# Display_LED.net
KiCad netlist of a schematic drawn in EAGLE
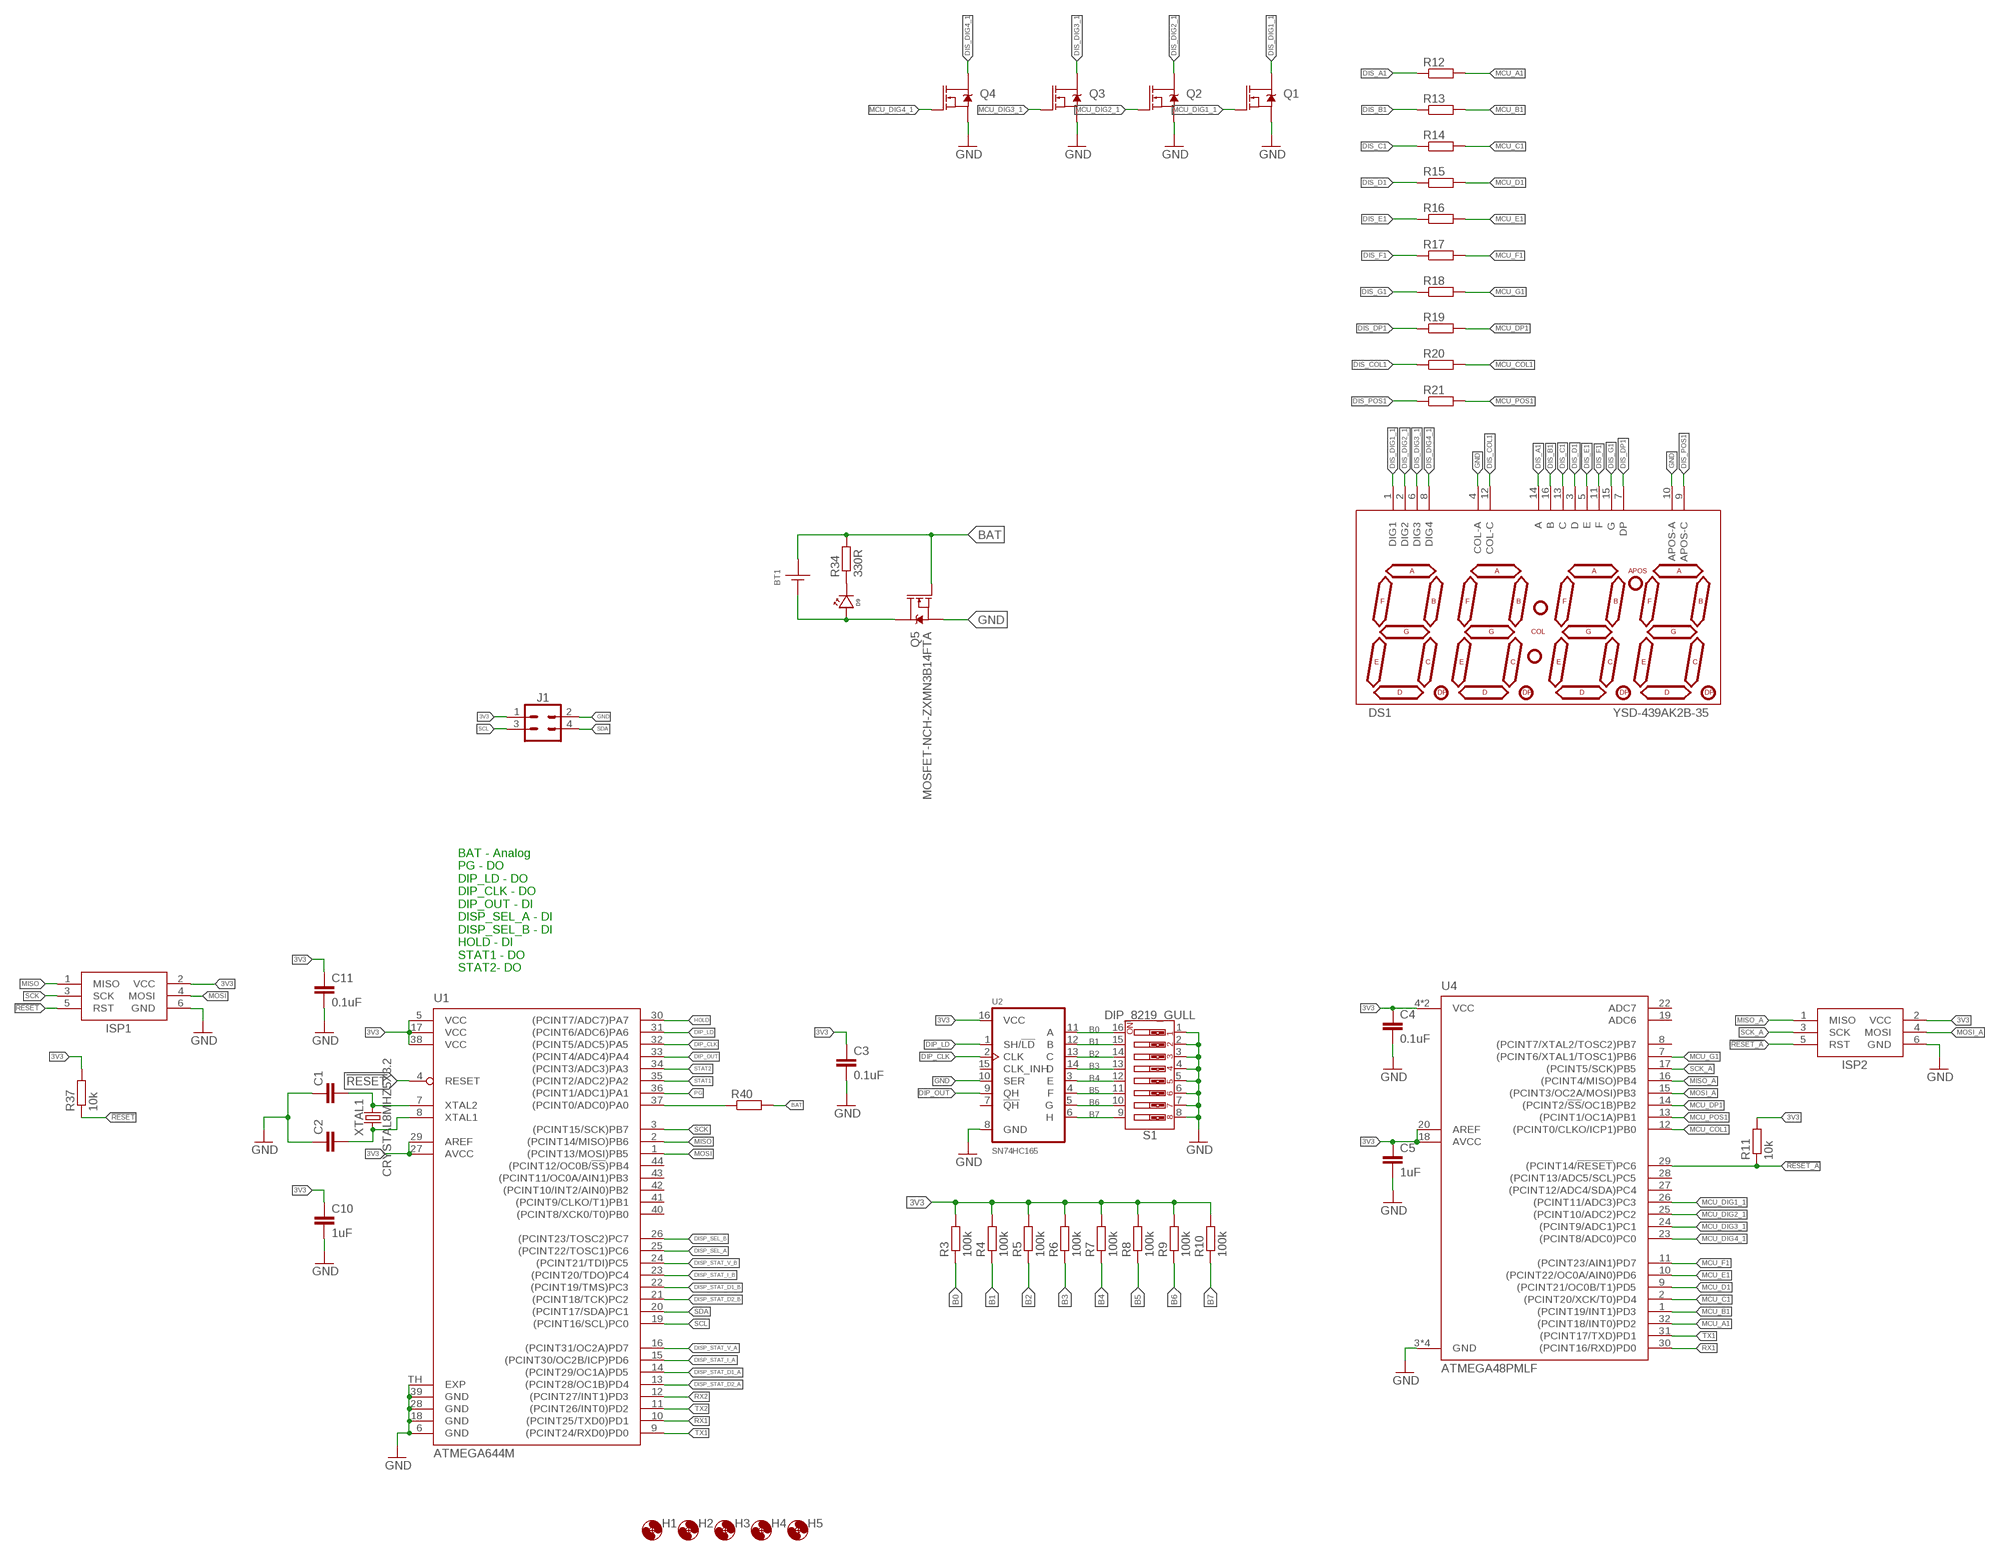
[diagram p0: schematic, sheet 1, part 1 of 2]
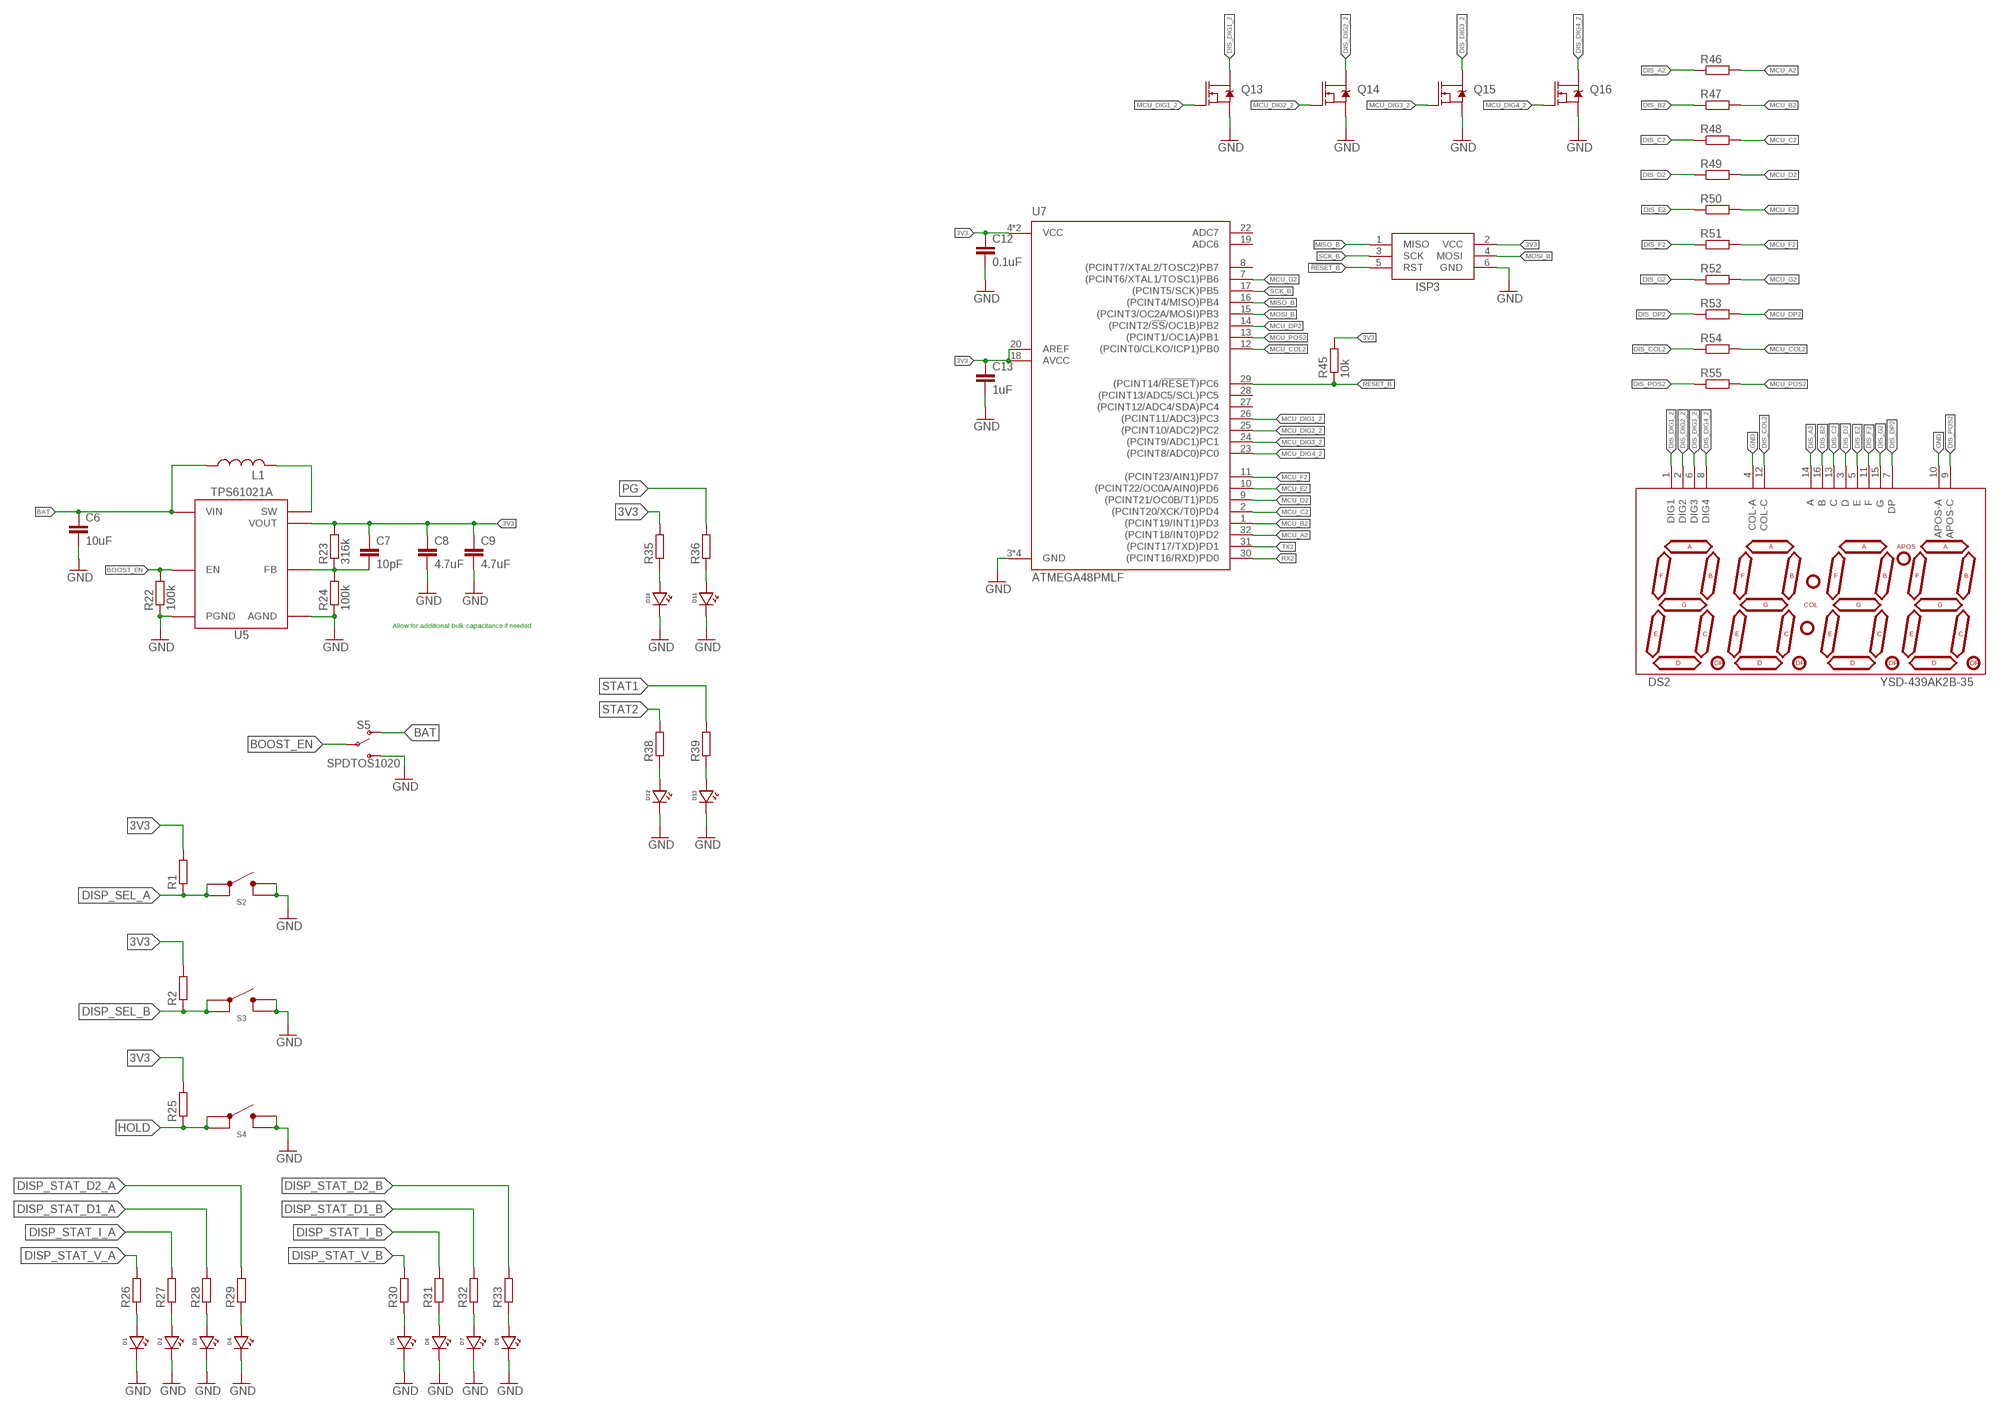
[diagram p1: schematic, sheet 1, part 2 of 2]

(export (version "E")
  (design (tool "Eeschema 10.0.6"))
  (components
    (comp (ref "BT1")
      (value "AACLIP")
      (footprint "eagle-import:BAT_AA_BK-92")
      (fields (field (name "MF") "MPD") (field (name "MPN") "BK-92"))
      (libsource (lib "eagle-import") (part "AACLIP"))
    )
    (comp (ref "C1")
      (value "C-EU12PFC0402")
      (footprint "eagle-import:C0402")
      (fields (field (name "MF") "TDK") (field (name "MPN") "CGA2B2C0G1H120J050BA"))
      (libsource (lib "eagle-import") (part "C-EUC040212PF"))
    )
    (comp (ref "C2")
      (value "C-EU12PFC0402")
      (footprint "eagle-import:C0402")
      (fields (field (name "MF") "TDK") (field (name "MPN") "CGA2B2C0G1H120J050BA"))
      (libsource (lib "eagle-import") (part "C-EUC040212PF"))
    )
    (comp (ref "C3")
      (value "0.1uF")
      (footprint "eagle-import:C0603")
      (fields (field (name "MF") "Murata") (field (name "MPN") "GCM188R71E104KA57D"))
      (libsource (lib "eagle-import") (part "C-EUC06030.1UF"))
    )
    (comp (ref "C4")
      (value "0.1uF")
      (footprint "eagle-import:C0603")
      (fields (field (name "MF") "Murata") (field (name "MPN") "GCM188R71E104KA57D"))
      (libsource (lib "eagle-import") (part "C-EUC06030.1UF"))
    )
    (comp (ref "C5")
      (value "1uF")
      (footprint "eagle-import:C0603")
      (fields (field (name "MF") "Yaiyo Yuden") (field (name "MPN") "EMK107BJ105KA-T"))
      (libsource (lib "eagle-import") (part "C-EUC06031UF"))
    )
    (comp (ref "C6")
      (value "10uF")
      (footprint "eagle-import:C0805")
      (fields (field (name "MF") "Murata") (field (name "MPN") "GRM21BR61C106KE15K"))
      (libsource (lib "eagle-import") (part "C-EUC080510UF"))
    )
    (comp (ref "C7")
      (value "10pF")
      (footprint "eagle-import:C0603")
      (fields (field (name "MF") "Yageo") (field (name "MPN") "CC0603JRNPO9BN100CC0603JRNPO9BN100"))
      (libsource (lib "eagle-import") (part "C-EUC060310PF"))
    )
    (comp (ref "C8")
      (value "4.7uF")
      (footprint "eagle-import:C0805")
      (fields (field (name "MF") "Kemet") (field (name "MPN") "C0805C475K4RACTU"))
      (libsource (lib "eagle-import") (part "C-EUC08054.7UF"))
    )
    (comp (ref "C9")
      (value "4.7uF")
      (footprint "eagle-import:C0805")
      (fields (field (name "MF") "Kemet") (field (name "MPN") "C0805C475K4RACTU"))
      (libsource (lib "eagle-import") (part "C-EUC08054.7UF"))
    )
    (comp (ref "C10")
      (value "1uF")
      (footprint "eagle-import:C0603")
      (fields (field (name "MF") "Yaiyo Yuden") (field (name "MPN") "EMK107BJ105KA-T"))
      (libsource (lib "eagle-import") (part "C-EUC06031UF"))
    )
    (comp (ref "C11")
      (value "0.1uF")
      (footprint "eagle-import:C0603")
      (fields (field (name "MF") "Yaiyo Yuden") (field (name "MPN") "EMK107BJ105KA-T"))
      (libsource (lib "eagle-import") (part "C-EUC06031UF"))
    )
    (comp (ref "C12")
      (value "0.1uF")
      (footprint "eagle-import:C0603")
      (fields (field (name "MF") "Murata") (field (name "MPN") "GCM188R71E104KA57D"))
      (libsource (lib "eagle-import") (part "C-EUC06030.1UF"))
    )
    (comp (ref "C13")
      (value "1uF")
      (footprint "eagle-import:C0603")
      (fields (field (name "MF") "Yaiyo Yuden") (field (name "MPN") "EMK107BJ105KA-T"))
      (libsource (lib "eagle-import") (part "C-EUC06031UF"))
    )
    (comp (ref "D1")
      (value "LED0603")
      (footprint "eagle-import:LED_0603")
      (libsource (lib "eagle-import") (part "LED0603"))
    )
    (comp (ref "D2")
      (value "LED0603")
      (footprint "eagle-import:LED_0603")
      (libsource (lib "eagle-import") (part "LED0603"))
    )
    (comp (ref "D3")
      (value "LED0603")
      (footprint "eagle-import:LED_0603")
      (libsource (lib "eagle-import") (part "LED0603"))
    )
    (comp (ref "D4")
      (value "LED0603")
      (footprint "eagle-import:LED_0603")
      (libsource (lib "eagle-import") (part "LED0603"))
    )
    (comp (ref "D5")
      (value "LED0603")
      (footprint "eagle-import:LED_0603")
      (libsource (lib "eagle-import") (part "LED0603"))
    )
    (comp (ref "D6")
      (value "LED0603")
      (footprint "eagle-import:LED_0603")
      (libsource (lib "eagle-import") (part "LED0603"))
    )
    (comp (ref "D7")
      (value "LED0603")
      (footprint "eagle-import:LED_0603")
      (libsource (lib "eagle-import") (part "LED0603"))
    )
    (comp (ref "D8")
      (value "LED0603")
      (footprint "eagle-import:LED_0603")
      (libsource (lib "eagle-import") (part "LED0603"))
    )
    (comp (ref "D9")
      (value "LED0603")
      (footprint "eagle-import:LED_0603")
      (libsource (lib "eagle-import") (part "LED0603"))
    )
    (comp (ref "D10")
      (value "LED0603")
      (footprint "eagle-import:LED_0603")
      (libsource (lib "eagle-import") (part "LED0603"))
    )
    (comp (ref "D11")
      (value "LED0603")
      (footprint "eagle-import:LED_0603")
      (libsource (lib "eagle-import") (part "LED0603"))
    )
    (comp (ref "D12")
      (value "LED0603")
      (footprint "eagle-import:LED_0603")
      (libsource (lib "eagle-import") (part "LED0603"))
    )
    (comp (ref "D13")
      (value "LED0603")
      (footprint "eagle-import:LED_0603")
      (libsource (lib "eagle-import") (part "LED0603"))
    )
    (comp (ref "DS1")
      (value "YSD-439AK2B-35")
      (footprint "eagle-import:7-SEGMENT-4DIGIT-YOUNGSUN")
      (libsource (lib "eagle-import") (part "LED_7-SEGMENT-4DIGIT-10MM-KGREEN"))
    )
    (comp (ref "DS2")
      (value "YSD-439AK2B-35")
      (footprint "eagle-import:7-SEGMENT-4DIGIT-YOUNGSUN")
      (libsource (lib "eagle-import") (part "LED_7-SEGMENT-4DIGIT-10MM-KGREEN"))
    )
    (comp (ref "H1")
      (value "MOUNTING_HOLE2_NP")
      (footprint "eagle-import:2_56")
      (fields (field (name "MPN") "DNP"))
      (libsource (lib "eagle-import") (part "MOUNTING_HOLE2_NP"))
    )
    (comp (ref "H2")
      (value "MOUNTING_HOLE2_NP")
      (footprint "eagle-import:2_56")
      (fields (field (name "MPN") "DNP"))
      (libsource (lib "eagle-import") (part "MOUNTING_HOLE2_NP"))
    )
    (comp (ref "H3")
      (value "MOUNTING_HOLE2_NP")
      (footprint "eagle-import:2_56")
      (fields (field (name "MPN") "DNP"))
      (libsource (lib "eagle-import") (part "MOUNTING_HOLE2_NP"))
    )
    (comp (ref "H4")
      (value "MOUNTING_HOLE2_NP")
      (footprint "eagle-import:2_56")
      (fields (field (name "MPN") "DNP"))
      (libsource (lib "eagle-import") (part "MOUNTING_HOLE2_NP"))
    )
    (comp (ref "H5")
      (value "MOUNTING_HOLE2_NP")
      (footprint "eagle-import:2_56")
      (fields (field (name "MPN") "DNP"))
      (libsource (lib "eagle-import") (part "MOUNTING_HOLE2_NP"))
    )
    (comp (ref "ISP1")
      (value "AVRISP-6")
      (footprint "eagle-import:AVRISP")
      (libsource (lib "eagle-import") (part "AVRISP-6"))
    )
    (comp (ref "ISP2")
      (value "AVRISP-6")
      (footprint "eagle-import:AVRISP")
      (libsource (lib "eagle-import") (part "AVRISP-6"))
    )
    (comp (ref "ISP3")
      (value "AVRISP-6")
      (footprint "eagle-import:AVRISP")
      (libsource (lib "eagle-import") (part "AVRISP-6"))
    )
    (comp (ref "J1")
      (value "CONN_2X2MIRCOFIT_RT")
      (footprint "eagle-import:2X2_MICROFIT_RT")
      (fields (field (name "MF") "Molex") (field (name "MPN") "0430450400"))
      (libsource (lib "eagle-import") (part "CONN_2X2MIRCOFIT_RT"))
    )
    (comp (ref "L1")
      (value "INDUCTORMAPI_3X3")
      (footprint "eagle-import:WE-MAPI(3X3)")
      (libsource (lib "eagle-import") (part "INDUCTORMAPI_3X3"))
    )
    (comp (ref "Q1")
      (value "MOSFET-NCH-2N7002P")
      (footprint "eagle-import:SOT23-3")
      (fields (field (name "MF") "Nexperia") (field (name "MPN") "2N7002P,215"))
      (libsource (lib "eagle-import") (part "MOSFET-NCH-2N7002P"))
    )
    (comp (ref "Q2")
      (value "MOSFET-NCH-2N7002P")
      (footprint "eagle-import:SOT23-3")
      (fields (field (name "MF") "Nexperia") (field (name "MPN") "2N7002P,215"))
      (libsource (lib "eagle-import") (part "MOSFET-NCH-2N7002P"))
    )
    (comp (ref "Q3")
      (value "MOSFET-NCH-2N7002P")
      (footprint "eagle-import:SOT23-3")
      (fields (field (name "MF") "Nexperia") (field (name "MPN") "2N7002P,215"))
      (libsource (lib "eagle-import") (part "MOSFET-NCH-2N7002P"))
    )
    (comp (ref "Q4")
      (value "MOSFET-NCH-2N7002P")
      (footprint "eagle-import:SOT23-3")
      (fields (field (name "MF") "Nexperia") (field (name "MPN") "2N7002P,215"))
      (libsource (lib "eagle-import") (part "MOSFET-NCH-2N7002P"))
    )
    (comp (ref "Q5")
      (value "MOSFET-NCH-ZXMN3B14FTA")
      (footprint "eagle-import:SOT23-3")
      (fields (field (name "MF") "Diodes Inc") (field (name "MPN") "ZXMN3B14FTA"))
      (libsource (lib "eagle-import") (part "MOSFET-NCH-ZXMN3B14FTA"))
    )
    (comp (ref "Q13")
      (value "MOSFET-NCH-2N7002P")
      (footprint "eagle-import:SOT23-3")
      (fields (field (name "MF") "Nexperia") (field (name "MPN") "2N7002P,215"))
      (libsource (lib "eagle-import") (part "MOSFET-NCH-2N7002P"))
    )
    (comp (ref "Q14")
      (value "MOSFET-NCH-2N7002P")
      (footprint "eagle-import:SOT23-3")
      (fields (field (name "MF") "Nexperia") (field (name "MPN") "2N7002P,215"))
      (libsource (lib "eagle-import") (part "MOSFET-NCH-2N7002P"))
    )
    (comp (ref "Q15")
      (value "MOSFET-NCH-2N7002P")
      (footprint "eagle-import:SOT23-3")
      (fields (field (name "MF") "Nexperia") (field (name "MPN") "2N7002P,215"))
      (libsource (lib "eagle-import") (part "MOSFET-NCH-2N7002P"))
    )
    (comp (ref "Q16")
      (value "MOSFET-NCH-2N7002P")
      (footprint "eagle-import:SOT23-3")
      (fields (field (name "MF") "Nexperia") (field (name "MPN") "2N7002P,215"))
      (libsource (lib "eagle-import") (part "MOSFET-NCH-2N7002P"))
    )
    (comp (ref "R1")
      (value "R-EU_10KR0603")
      (footprint "eagle-import:R0603")
      (fields
        (field (name "MF") "Yageo")
        (field (name "MPN") "RC0603FR-0710KL")
        (field (name "VALUE_PART") "10k")
      )
      (libsource (lib "eagle-import") (part "R-EU_R060310K"))
    )
    (comp (ref "R2")
      (value "R-EU_10KR0603")
      (footprint "eagle-import:R0603")
      (fields
        (field (name "MF") "Yageo")
        (field (name "MPN") "RC0603FR-0710KL")
        (field (name "VALUE_PART") "10k")
      )
      (libsource (lib "eagle-import") (part "R-EU_R060310K"))
    )
    (comp (ref "R3")
      (value "100k")
      (footprint "eagle-import:R0603")
      (fields (field (name "MF") "Yageo") (field (name "MPN") "RC0603FR-07100KL"))
      (libsource (lib "eagle-import") (part "R-EU_R0603100K"))
    )
    (comp (ref "R4")
      (value "100k")
      (footprint "eagle-import:R0603")
      (fields (field (name "MF") "Yageo") (field (name "MPN") "RC0603FR-07100KL"))
      (libsource (lib "eagle-import") (part "R-EU_R0603100K"))
    )
    (comp (ref "R5")
      (value "100k")
      (footprint "eagle-import:R0603")
      (fields (field (name "MF") "Yageo") (field (name "MPN") "RC0603FR-07100KL"))
      (libsource (lib "eagle-import") (part "R-EU_R0603100K"))
    )
    (comp (ref "R6")
      (value "100k")
      (footprint "eagle-import:R0603")
      (fields (field (name "MF") "Yageo") (field (name "MPN") "RC0603FR-07100KL"))
      (libsource (lib "eagle-import") (part "R-EU_R0603100K"))
    )
    (comp (ref "R7")
      (value "100k")
      (footprint "eagle-import:R0603")
      (fields (field (name "MF") "Yageo") (field (name "MPN") "RC0603FR-07100KL"))
      (libsource (lib "eagle-import") (part "R-EU_R0603100K"))
    )
    (comp (ref "R8")
      (value "100k")
      (footprint "eagle-import:R0603")
      (fields (field (name "MF") "Yageo") (field (name "MPN") "RC0603FR-07100KL"))
      (libsource (lib "eagle-import") (part "R-EU_R0603100K"))
    )
    (comp (ref "R9")
      (value "100k")
      (footprint "eagle-import:R0603")
      (fields (field (name "MF") "Yageo") (field (name "MPN") "RC0603FR-07100KL"))
      (libsource (lib "eagle-import") (part "R-EU_R0603100K"))
    )
    (comp (ref "R10")
      (value "100k")
      (footprint "eagle-import:R0603")
      (fields (field (name "MF") "Yageo") (field (name "MPN") "RC0603FR-07100KL"))
      (libsource (lib "eagle-import") (part "R-EU_R0603100K"))
    )
    (comp (ref "R11")
      (value "10k")
      (footprint "eagle-import:R0603")
      (fields (field (name "MF") "Yageo") (field (name "MPN") "RC0603FR-0710KL"))
      (libsource (lib "eagle-import") (part "R-EU_R060310K"))
    )
    (comp (ref "R12")
      (value "R-EU_330R0603")
      (footprint "eagle-import:R0603")
      (fields
        (field (name "MF") "Yageo")
        (field (name "MPN") "RC0603FR-07330RL")
        (field (name "VALUE_PART") "330")
      )
      (libsource (lib "eagle-import") (part "R-EU_R0603330"))
    )
    (comp (ref "R13")
      (value "R-EU_330R0603")
      (footprint "eagle-import:R0603")
      (fields
        (field (name "MF") "Yageo")
        (field (name "MPN") "RC0603FR-07330RL")
        (field (name "VALUE_PART") "330")
      )
      (libsource (lib "eagle-import") (part "R-EU_R0603330"))
    )
    (comp (ref "R14")
      (value "R-EU_330R0603")
      (footprint "eagle-import:R0603")
      (fields
        (field (name "MF") "Yageo")
        (field (name "MPN") "RC0603FR-07330RL")
        (field (name "VALUE_PART") "330")
      )
      (libsource (lib "eagle-import") (part "R-EU_R0603330"))
    )
    (comp (ref "R15")
      (value "R-EU_330R0603")
      (footprint "eagle-import:R0603")
      (fields
        (field (name "MF") "Yageo")
        (field (name "MPN") "RC0603FR-07330RL")
        (field (name "VALUE_PART") "330")
      )
      (libsource (lib "eagle-import") (part "R-EU_R0603330"))
    )
    (comp (ref "R16")
      (value "R-EU_330R0603")
      (footprint "eagle-import:R0603")
      (fields
        (field (name "MF") "Yageo")
        (field (name "MPN") "RC0603FR-07330RL")
        (field (name "VALUE_PART") "330")
      )
      (libsource (lib "eagle-import") (part "R-EU_R0603330"))
    )
    (comp (ref "R17")
      (value "R-EU_330R0603")
      (footprint "eagle-import:R0603")
      (fields
        (field (name "MF") "Yageo")
        (field (name "MPN") "RC0603FR-07330RL")
        (field (name "VALUE_PART") "330")
      )
      (libsource (lib "eagle-import") (part "R-EU_R0603330"))
    )
    (comp (ref "R18")
      (value "R-EU_330R0603")
      (footprint "eagle-import:R0603")
      (fields
        (field (name "MF") "Yageo")
        (field (name "MPN") "RC0603FR-07330RL")
        (field (name "VALUE_PART") "330")
      )
      (libsource (lib "eagle-import") (part "R-EU_R0603330"))
    )
    (comp (ref "R19")
      (value "R-EU_330R0603")
      (footprint "eagle-import:R0603")
      (fields
        (field (name "MF") "Yageo")
        (field (name "MPN") "RC0603FR-07330RL")
        (field (name "VALUE_PART") "330")
      )
      (libsource (lib "eagle-import") (part "R-EU_R0603330"))
    )
    (comp (ref "R20")
      (value "R-EU_330R0603")
      (footprint "eagle-import:R0603")
      (fields
        (field (name "MF") "Yageo")
        (field (name "MPN") "RC0603FR-07330RL")
        (field (name "VALUE_PART") "330")
      )
      (libsource (lib "eagle-import") (part "R-EU_R0603330"))
    )
    (comp (ref "R21")
      (value "R-EU_330R0603")
      (footprint "eagle-import:R0603")
      (fields
        (field (name "MF") "Yageo")
        (field (name "MPN") "RC0603FR-07330RL")
        (field (name "VALUE_PART") "330")
      )
      (libsource (lib "eagle-import") (part "R-EU_R0603330"))
    )
    (comp (ref "R22")
      (value "100k")
      (footprint "eagle-import:R0603")
      (fields (field (name "MF") "Yageo") (field (name "MPN") "RC0603FR-07100KL"))
      (libsource (lib "eagle-import") (part "R-EU_R0603100K"))
    )
    (comp (ref "R23")
      (value "316k")
      (footprint "eagle-import:R0603")
      (fields (field (name "MF") "Yageo") (field (name "MPN") "RC0603FR-07316KL"))
      (libsource (lib "eagle-import") (part "R-EU_R0603316K"))
    )
    (comp (ref "R24")
      (value "100k")
      (footprint "eagle-import:R0603")
      (fields (field (name "MF") "Yageo") (field (name "MPN") "RC0603FR-07100KL"))
      (libsource (lib "eagle-import") (part "R-EU_R0603100K"))
    )
    (comp (ref "R25")
      (value "R-EU_10KR0603")
      (footprint "eagle-import:R0603")
      (fields
        (field (name "MF") "Yageo")
        (field (name "MPN") "RC0603FR-0710KL")
        (field (name "VALUE_PART") "10k")
      )
      (libsource (lib "eagle-import") (part "R-EU_R060310K"))
    )
    (comp (ref "R26")
      (value "R-EU_330R0603")
      (footprint "eagle-import:R0603")
      (fields
        (field (name "MF") "Yageo")
        (field (name "MPN") "RC0603FR-07330RL")
        (field (name "VALUE_PART") "330")
      )
      (libsource (lib "eagle-import") (part "R-EU_R0603330"))
    )
    (comp (ref "R27")
      (value "R-EU_330R0603")
      (footprint "eagle-import:R0603")
      (fields
        (field (name "MF") "Yageo")
        (field (name "MPN") "RC0603FR-07330RL")
        (field (name "VALUE_PART") "330")
      )
      (libsource (lib "eagle-import") (part "R-EU_R0603330"))
    )
    (comp (ref "R28")
      (value "R-EU_330R0603")
      (footprint "eagle-import:R0603")
      (fields
        (field (name "MF") "Yageo")
        (field (name "MPN") "RC0603FR-07330RL")
        (field (name "VALUE_PART") "330")
      )
      (libsource (lib "eagle-import") (part "R-EU_R0603330"))
    )
    (comp (ref "R29")
      (value "R-EU_330R0603")
      (footprint "eagle-import:R0603")
      (fields
        (field (name "MF") "Yageo")
        (field (name "MPN") "RC0603FR-07330RL")
        (field (name "VALUE_PART") "330")
      )
      (libsource (lib "eagle-import") (part "R-EU_R0603330"))
    )
    (comp (ref "R30")
      (value "R-EU_330R0603")
      (footprint "eagle-import:R0603")
      (fields
        (field (name "MF") "Yageo")
        (field (name "MPN") "RC0603FR-07330RL")
        (field (name "VALUE_PART") "330")
      )
      (libsource (lib "eagle-import") (part "R-EU_R0603330"))
    )
    (comp (ref "R31")
      (value "R-EU_330R0603")
      (footprint "eagle-import:R0603")
      (fields
        (field (name "MF") "Yageo")
        (field (name "MPN") "RC0603FR-07330RL")
        (field (name "VALUE_PART") "330")
      )
      (libsource (lib "eagle-import") (part "R-EU_R0603330"))
    )
    (comp (ref "R32")
      (value "R-EU_330R0603")
      (footprint "eagle-import:R0603")
      (fields
        (field (name "MF") "Yageo")
        (field (name "MPN") "RC0603FR-07330RL")
        (field (name "VALUE_PART") "330")
      )
      (libsource (lib "eagle-import") (part "R-EU_R0603330"))
    )
    (comp (ref "R33")
      (value "R-EU_330R0603")
      (footprint "eagle-import:R0603")
      (fields
        (field (name "MF") "Yageo")
        (field (name "MPN") "RC0603FR-07330RL")
        (field (name "VALUE_PART") "330")
      )
      (libsource (lib "eagle-import") (part "R-EU_R0603330"))
    )
    (comp (ref "R34")
      (value "330R")
      (footprint "eagle-import:R0603")
      (fields
        (field (name "MF") "Yageo")
        (field (name "MPN") "RC0603FR-07330RL")
        (field (name "VALUE_PART") "330")
      )
      (libsource (lib "eagle-import") (part "R-EU_R0603330"))
    )
    (comp (ref "R35")
      (value "R-EU_330R0603")
      (footprint "eagle-import:R0603")
      (fields
        (field (name "MF") "Yageo")
        (field (name "MPN") "RC0603FR-07330RL")
        (field (name "VALUE_PART") "330")
      )
      (libsource (lib "eagle-import") (part "R-EU_R0603330"))
    )
    (comp (ref "R36")
      (value "R-EU_330R0603")
      (footprint "eagle-import:R0603")
      (fields
        (field (name "MF") "Yageo")
        (field (name "MPN") "RC0603FR-07330RL")
        (field (name "VALUE_PART") "330")
      )
      (libsource (lib "eagle-import") (part "R-EU_R0603330"))
    )
    (comp (ref "R37")
      (value "10k")
      (footprint "eagle-import:R0603")
      (fields (field (name "MF") "Yageo") (field (name "MPN") "RC0603FR-0710KL"))
      (libsource (lib "eagle-import") (part "R-EU_R060310K"))
    )
    (comp (ref "R38")
      (value "R-EU_330R0603")
      (footprint "eagle-import:R0603")
      (fields
        (field (name "MF") "Yageo")
        (field (name "MPN") "RC0603FR-07330RL")
        (field (name "VALUE_PART") "330")
      )
      (libsource (lib "eagle-import") (part "R-EU_R0603330"))
    )
    (comp (ref "R39")
      (value "R-EU_330R0603")
      (footprint "eagle-import:R0603")
      (fields
        (field (name "MF") "Yageo")
        (field (name "MPN") "RC0603FR-07330RL")
        (field (name "VALUE_PART") "330")
      )
      (libsource (lib "eagle-import") (part "R-EU_R0603330"))
    )
    (comp (ref "R40")
      (value "R-EU_1KR0603")
      (footprint "eagle-import:R0603")
      (fields
        (field (name "MF") "Yageo")
        (field (name "MPN") "AC0603FR-071KL")
        (field (name "VALUE_PART") "1k")
      )
      (libsource (lib "eagle-import") (part "R-EU_R06031K"))
    )
    (comp (ref "R45")
      (value "10k")
      (footprint "eagle-import:R0603")
      (fields (field (name "MF") "Yageo") (field (name "MPN") "RC0603FR-0710KL"))
      (libsource (lib "eagle-import") (part "R-EU_R060310K"))
    )
    (comp (ref "R46")
      (value "R-EU_330R0603")
      (footprint "eagle-import:R0603")
      (fields
        (field (name "MF") "Yageo")
        (field (name "MPN") "RC0603FR-07330RL")
        (field (name "VALUE_PART") "330")
      )
      (libsource (lib "eagle-import") (part "R-EU_R0603330"))
    )
    (comp (ref "R47")
      (value "R-EU_330R0603")
      (footprint "eagle-import:R0603")
      (fields
        (field (name "MF") "Yageo")
        (field (name "MPN") "RC0603FR-07330RL")
        (field (name "VALUE_PART") "330")
      )
      (libsource (lib "eagle-import") (part "R-EU_R0603330"))
    )
    (comp (ref "R48")
      (value "R-EU_330R0603")
      (footprint "eagle-import:R0603")
      (fields
        (field (name "MF") "Yageo")
        (field (name "MPN") "RC0603FR-07330RL")
        (field (name "VALUE_PART") "330")
      )
      (libsource (lib "eagle-import") (part "R-EU_R0603330"))
    )
    (comp (ref "R49")
      (value "R-EU_330R0603")
      (footprint "eagle-import:R0603")
      (fields
        (field (name "MF") "Yageo")
        (field (name "MPN") "RC0603FR-07330RL")
        (field (name "VALUE_PART") "330")
      )
      (libsource (lib "eagle-import") (part "R-EU_R0603330"))
    )
    (comp (ref "R50")
      (value "R-EU_330R0603")
      (footprint "eagle-import:R0603")
      (fields
        (field (name "MF") "Yageo")
        (field (name "MPN") "RC0603FR-07330RL")
        (field (name "VALUE_PART") "330")
      )
      (libsource (lib "eagle-import") (part "R-EU_R0603330"))
    )
    (comp (ref "R51")
      (value "R-EU_330R0603")
      (footprint "eagle-import:R0603")
      (fields
        (field (name "MF") "Yageo")
        (field (name "MPN") "RC0603FR-07330RL")
        (field (name "VALUE_PART") "330")
      )
      (libsource (lib "eagle-import") (part "R-EU_R0603330"))
    )
    (comp (ref "R52")
      (value "R-EU_330R0603")
      (footprint "eagle-import:R0603")
      (fields
        (field (name "MF") "Yageo")
        (field (name "MPN") "RC0603FR-07330RL")
        (field (name "VALUE_PART") "330")
      )
      (libsource (lib "eagle-import") (part "R-EU_R0603330"))
    )
    (comp (ref "R53")
      (value "R-EU_330R0603")
      (footprint "eagle-import:R0603")
      (fields
        (field (name "MF") "Yageo")
        (field (name "MPN") "RC0603FR-07330RL")
        (field (name "VALUE_PART") "330")
      )
      (libsource (lib "eagle-import") (part "R-EU_R0603330"))
    )
    (comp (ref "R54")
      (value "R-EU_330R0603")
      (footprint "eagle-import:R0603")
      (fields
        (field (name "MF") "Yageo")
        (field (name "MPN") "RC0603FR-07330RL")
        (field (name "VALUE_PART") "330")
      )
      (libsource (lib "eagle-import") (part "R-EU_R0603330"))
    )
    (comp (ref "R55")
      (value "R-EU_330R0603")
      (footprint "eagle-import:R0603")
      (fields
        (field (name "MF") "Yageo")
        (field (name "MPN") "RC0603FR-07330RL")
        (field (name "VALUE_PART") "330")
      )
      (libsource (lib "eagle-import") (part "R-EU_R0603330"))
    )
    (comp (ref "S1")
      (value "DIP_8219_GULL")
      (footprint "eagle-import:219-8_GULLWING_DIP-CTS")
      (fields (field (name "MF") "CTS") (field (name "MPN") "219-8MSTR"))
      (libsource (lib "eagle-import") (part "DIP_8219_GULL"))
    )
    (comp (ref "S2")
      (value "BUTTON6X6")
      (footprint "eagle-import:SWITCH_6MM")
      (libsource (lib "eagle-import") (part "BUTTON6X6"))
    )
    (comp (ref "S3")
      (value "BUTTON6X6")
      (footprint "eagle-import:SWITCH_6MM")
      (libsource (lib "eagle-import") (part "BUTTON6X6"))
    )
    (comp (ref "S4")
      (value "BUTTON6X6")
      (footprint "eagle-import:SWITCH_6MM")
      (libsource (lib "eagle-import") (part "BUTTON6X6"))
    )
    (comp (ref "S5")
      (value "SPDTOS1020")
      (footprint "eagle-import:OS102011MS2QN1")
      (libsource (lib "eagle-import") (part "SPDTOS1020"))
    )
    (comp (ref "U1")
      (value "ATMEGA644M")
      (footprint "eagle-import:MLF44-TH")
      (fields (field (name "MF") "Atmel") (field (name "MPN") "ATMEGA644PA-MUR"))
      (libsource (lib "eagle-import") (part "ATMEGA644M"))
    )
    (comp (ref "U2")
      (value "SN74HC165PW")
      (footprint "eagle-import:TSSOP16")
      (fields (field (name "MF") "TI") (field (name "MPN") "SN74HC165PWR"))
      (libsource (lib "eagle-import") (part "SN74HC165PW"))
    )
    (comp (ref "U4")
      (value "ATMEGA48PMLF")
      (footprint "eagle-import:MLF32-5X5")
      (fields (field (name "MF") "Microchip") (field (name "MPN") "ATMEGA48PA-MNR"))
      (libsource (lib "eagle-import") (part "ATMEGA48PMLF"))
    )
    (comp (ref "U5")
      (value "TPS61021A")
      (footprint "eagle-import:DSG0008A")
      (fields (field (name "MF") "TI") (field (name "MPN") "TPS61021ADSGT"))
      (libsource (lib "eagle-import") (part "TPS61021A"))
    )
    (comp (ref "U7")
      (value "ATMEGA48PMLF")
      (footprint "eagle-import:MLF32-5X5")
      (fields (field (name "MF") "Microchip") (field (name "MPN") "ATMEGA48PA-MNR"))
      (libsource (lib "eagle-import") (part "ATMEGA48PMLF"))
    )
    (comp (ref "XTAL1")
      (value "CRYSTAL8MHZ5X3.2")
      (footprint "eagle-import:CRYSTAL_5X3.2_2-SMD")
      (fields (field (name "MF") "TXC") (field (name "MPN") "7A-8.000MAAE-T"))
      (libsource (lib "eagle-import") (part "CRYSTAL5X3.28MHZ"))
    )
  )
  (nets
    (net (code "1") (name "/~{RESET_A}") (class "Default")
      (node (ref "ISP2") (pin "5") (pinfunction "RST_5") (pintype "output"))
      (node (ref "R11") (pin "1") (pinfunction "1_1") (pintype "passive"))
      (node (ref "U4") (pin "29") (pinfunction "(PCINT14/~{RESET})PC6_29") (pintype "bidirectional"))
    )
    (net (code "2") (name "/~{RESET_B}") (class "Default")
      (node (ref "ISP3") (pin "5") (pinfunction "RST_5") (pintype "output"))
      (node (ref "R45") (pin "1") (pinfunction "1_1") (pintype "passive"))
      (node (ref "U7") (pin "29") (pinfunction "(PCINT14/~{RESET})PC6_29") (pintype "bidirectional"))
    )
    (net (code "3") (name "/~{RESET}") (class "Default")
      (node (ref "ISP1") (pin "5") (pinfunction "RST_5") (pintype "output"))
      (node (ref "R37") (pin "1") (pinfunction "1_1") (pintype "passive"))
      (node (ref "U1") (pin "4") (pinfunction "RESET_4") (pintype "input"))
    )
    (net (code "4") (name "3V3") (class "Default")
      (node (ref "C10") (pin "1") (pinfunction "1_1") (pintype "passive"))
      (node (ref "C11") (pin "1") (pinfunction "1_1") (pintype "passive"))
      (node (ref "C12") (pin "1") (pinfunction "1_1") (pintype "passive"))
      (node (ref "C13") (pin "1") (pinfunction "1_1") (pintype "passive"))
      (node (ref "C3") (pin "1") (pinfunction "1_1") (pintype "passive"))
      (node (ref "C4") (pin "1") (pinfunction "1_1") (pintype "passive"))
      (node (ref "C5") (pin "1") (pinfunction "1_1") (pintype "passive"))
      (node (ref "C7") (pin "1") (pinfunction "1_1") (pintype "passive"))
      (node (ref "C8") (pin "1") (pinfunction "1_1") (pintype "passive"))
      (node (ref "C9") (pin "1") (pinfunction "1_1") (pintype "passive"))
      (node (ref "ISP1") (pin "2") (pinfunction "VCC_2") (pintype "power_in"))
      (node (ref "ISP2") (pin "2") (pinfunction "VCC_2") (pintype "power_in"))
      (node (ref "ISP3") (pin "2") (pinfunction "VCC_2") (pintype "power_in"))
      (node (ref "J1") (pin "1") (pinfunction "1_1") (pintype "bidirectional"))
      (node (ref "R1") (pin "2") (pinfunction "2_2") (pintype "passive"))
      (node (ref "R10") (pin "2") (pinfunction "2_2") (pintype "passive"))
      (node (ref "R11") (pin "2") (pinfunction "2_2") (pintype "passive"))
      (node (ref "R2") (pin "2") (pinfunction "2_2") (pintype "passive"))
      (node (ref "R23") (pin "2") (pinfunction "2_2") (pintype "passive"))
      (node (ref "R25") (pin "2") (pinfunction "2_2") (pintype "passive"))
      (node (ref "R3") (pin "2") (pinfunction "2_2") (pintype "passive"))
      (node (ref "R35") (pin "2") (pinfunction "2_2") (pintype "passive"))
      (node (ref "R37") (pin "2") (pinfunction "2_2") (pintype "passive"))
      (node (ref "R4") (pin "2") (pinfunction "2_2") (pintype "passive"))
      (node (ref "R45") (pin "2") (pinfunction "2_2") (pintype "passive"))
      (node (ref "R5") (pin "2") (pinfunction "2_2") (pintype "passive"))
      (node (ref "R6") (pin "2") (pinfunction "2_2") (pintype "passive"))
      (node (ref "R7") (pin "2") (pinfunction "2_2") (pintype "passive"))
      (node (ref "R8") (pin "2") (pinfunction "2_2") (pintype "passive"))
      (node (ref "R9") (pin "2") (pinfunction "2_2") (pintype "passive"))
      (node (ref "U1") (pin "17") (pinfunction "VCC_17") (pintype "power_in"))
      (node (ref "U1") (pin "27") (pinfunction "AVCC_27") (pintype "power_in"))
      (node (ref "U1") (pin "29") (pinfunction "AREF_29") (pintype "passive"))
      (node (ref "U1") (pin "38") (pinfunction "VCC_38") (pintype "power_in"))
      (node (ref "U1") (pin "5") (pinfunction "VCC_5") (pintype "power_in"))
      (node (ref "U2") (pin "16") (pinfunction "VCC_16") (pintype "power_in"))
      (node (ref "U4") (pin "18") (pinfunction "AVCC_18") (pintype "power_in"))
      (node (ref "U4") (pin "20") (pinfunction "AREF_20") (pintype "passive"))
      (node (ref "U4") (pin "4") (pinfunction "VCC_4") (pintype "power_in"))
      (node (ref "U4") (pin "6") (pinfunction "VCC_6") (pintype "power_in"))
      (node (ref "U5") (pin "3") (pinfunction "VOUT_3") (pintype "power_in"))
      (node (ref "U5") (pin "4") (pinfunction "VOUT_4") (pintype "power_in"))
      (node (ref "U7") (pin "18") (pinfunction "AVCC_18") (pintype "power_in"))
      (node (ref "U7") (pin "20") (pinfunction "AREF_20") (pintype "passive"))
      (node (ref "U7") (pin "4") (pinfunction "VCC_4") (pintype "power_in"))
      (node (ref "U7") (pin "6") (pinfunction "VCC_6") (pintype "power_in"))
    )
    (net (code "5") (name "B0") (class "Default")
      (node (ref "R3") (pin "1") (pinfunction "1_1") (pintype "passive"))
      (node (ref "S1") (pin "16") (pinfunction "16_16") (pintype "passive"))
      (node (ref "U2") (pin "11") (pinfunction "A_11") (pintype "tri_state"))
    )
    (net (code "6") (name "B1") (class "Default")
      (node (ref "R4") (pin "1") (pinfunction "1_1") (pintype "passive"))
      (node (ref "S1") (pin "15") (pinfunction "15_15") (pintype "passive"))
      (node (ref "U2") (pin "12") (pinfunction "B_12") (pintype "tri_state"))
    )
    (net (code "7") (name "B2") (class "Default")
      (node (ref "R5") (pin "1") (pinfunction "1_1") (pintype "passive"))
      (node (ref "S1") (pin "14") (pinfunction "14_14") (pintype "passive"))
      (node (ref "U2") (pin "13") (pinfunction "C_13") (pintype "tri_state"))
    )
    (net (code "8") (name "B3") (class "Default")
      (node (ref "R6") (pin "1") (pinfunction "1_1") (pintype "passive"))
      (node (ref "S1") (pin "13") (pinfunction "13_13") (pintype "passive"))
      (node (ref "U2") (pin "14") (pinfunction "D_14") (pintype "tri_state"))
    )
    (net (code "9") (name "B4") (class "Default")
      (node (ref "R7") (pin "1") (pinfunction "1_1") (pintype "passive"))
      (node (ref "S1") (pin "12") (pinfunction "12_12") (pintype "passive"))
      (node (ref "U2") (pin "3") (pinfunction "E_3") (pintype "tri_state"))
    )
    (net (code "10") (name "B5") (class "Default")
      (node (ref "R8") (pin "1") (pinfunction "1_1") (pintype "passive"))
      (node (ref "S1") (pin "11") (pinfunction "11_11") (pintype "passive"))
      (node (ref "U2") (pin "4") (pinfunction "F_4") (pintype "tri_state"))
    )
    (net (code "11") (name "B6") (class "Default")
      (node (ref "R9") (pin "1") (pinfunction "1_1") (pintype "passive"))
      (node (ref "S1") (pin "10") (pinfunction "10_10") (pintype "passive"))
      (node (ref "U2") (pin "5") (pinfunction "G_5") (pintype "tri_state"))
    )
    (net (code "12") (name "B7") (class "Default")
      (node (ref "R10") (pin "1") (pinfunction "1_1") (pintype "passive"))
      (node (ref "S1") (pin "9") (pinfunction "9_9") (pintype "passive"))
      (node (ref "U2") (pin "6") (pinfunction "H_6") (pintype "tri_state"))
    )
    (net (code "13") (name "BAT") (class "Default")
      (node (ref "BT1") (pin "POS@1") (pinfunction "+_POS@1") (pintype "power_in"))
      (node (ref "BT1") (pin "POS@2") (pinfunction "+_POS@2") (pintype "power_in"))
      (node (ref "C6") (pin "1") (pinfunction "1_1") (pintype "passive"))
      (node (ref "L1") (pin "P$1") (pinfunction "1_P$1") (pintype "passive"))
      (node (ref "Q5") (pin "1") (pinfunction "G_1") (pintype "bidirectional"))
      (node (ref "R34") (pin "2") (pinfunction "2_2") (pintype "passive"))
      (node (ref "R40") (pin "2") (pinfunction "2_2") (pintype "passive"))
      (node (ref "S5") (pin "1") (pinfunction "O_1") (pintype "passive"))
      (node (ref "U5") (pin "8") (pinfunction "VIN_8") (pintype "power_in"))
    )
    (net (code "14") (name "BOOST_EN") (class "Default")
      (node (ref "R22") (pin "2") (pinfunction "2_2") (pintype "passive"))
      (node (ref "S5") (pin "2") (pinfunction "P_2") (pintype "passive"))
      (node (ref "U5") (pin "5") (pinfunction "EN_5") (pintype "input"))
    )
    (net (code "15") (name "DIP_CLK") (class "Default")
      (node (ref "U1") (pin "32") (pinfunction "(PCINT5/ADC5)PA5_32") (pintype "bidirectional"))
      (node (ref "U2") (pin "2") (pinfunction "CLK_2") (pintype "input"))
    )
    (net (code "16") (name "DIP_LD") (class "Default")
      (node (ref "U1") (pin "31") (pinfunction "(PCINT6/ADC6)PA6_31") (pintype "bidirectional"))
      (node (ref "U2") (pin "1") (pinfunction "SH/~{LD}_1") (pintype "input"))
    )
    (net (code "17") (name "DIP_OUT") (class "Default")
      (node (ref "U1") (pin "33") (pinfunction "(PCINT4/ADC4)PA4_33") (pintype "bidirectional"))
      (node (ref "U2") (pin "9") (pinfunction "QH_9") (pintype "tri_state"))
    )
    (net (code "18") (name "DISP_SEL_A") (class "Default")
      (node (ref "R1") (pin "1") (pinfunction "1_1") (pintype "passive"))
      (node (ref "S2") (pin "1") (pinfunction "1_1") (pintype "bidirectional"))
      (node (ref "S2") (pin "2") (pinfunction "2_2") (pintype "bidirectional"))
      (node (ref "U1") (pin "25") (pinfunction "(PCINT22/TOSC1)PC6_25") (pintype "output"))
    )
    (net (code "19") (name "DISP_SEL_B") (class "Default")
      (node (ref "R2") (pin "1") (pinfunction "1_1") (pintype "passive"))
      (node (ref "S3") (pin "1") (pinfunction "1_1") (pintype "bidirectional"))
      (node (ref "S3") (pin "2") (pinfunction "2_2") (pintype "bidirectional"))
      (node (ref "U1") (pin "26") (pinfunction "(PCINT23/TOSC2)PC7_26") (pintype "output"))
    )
    (net (code "20") (name "DISP_STAT_D1_A") (class "Default")
      (node (ref "R28") (pin "2") (pinfunction "2_2") (pintype "passive"))
      (node (ref "U1") (pin "14") (pinfunction "(PCINT29/OC1A)PD5_14") (pintype "bidirectional"))
    )
    (net (code "21") (name "DISP_STAT_D1_B") (class "Default")
      (node (ref "R32") (pin "2") (pinfunction "2_2") (pintype "passive"))
      (node (ref "U1") (pin "22") (pinfunction "(PCINT19/TMS)PC3_22") (pintype "output"))
    )
    (net (code "22") (name "DISP_STAT_D2_A") (class "Default")
      (node (ref "R29") (pin "2") (pinfunction "2_2") (pintype "passive"))
      (node (ref "U1") (pin "13") (pinfunction "(PCINT28/OC1B)PD4_13") (pintype "bidirectional"))
    )
    (net (code "23") (name "DISP_STAT_D2_B") (class "Default")
      (node (ref "R33") (pin "2") (pinfunction "2_2") (pintype "passive"))
      (node (ref "U1") (pin "21") (pinfunction "(PCINT18/TCK)PC2_21") (pintype "output"))
    )
    (net (code "24") (name "DISP_STAT_I_A") (class "Default")
      (node (ref "R27") (pin "2") (pinfunction "2_2") (pintype "passive"))
      (node (ref "U1") (pin "15") (pinfunction "(PCINT30/OC2B/ICP)PD6_15") (pintype "bidirectional"))
    )
    (net (code "25") (name "DISP_STAT_I_B") (class "Default")
      (node (ref "R31") (pin "2") (pinfunction "2_2") (pintype "passive"))
      (node (ref "U1") (pin "23") (pinfunction "(PCINT20/TDO)PC4_23") (pintype "output"))
    )
    (net (code "26") (name "DISP_STAT_V_A") (class "Default")
      (node (ref "R26") (pin "2") (pinfunction "2_2") (pintype "passive"))
      (node (ref "U1") (pin "16") (pinfunction "(PCINT31/OC2A)PD7_16") (pintype "bidirectional"))
    )
    (net (code "27") (name "DISP_STAT_V_B") (class "Default")
      (node (ref "R30") (pin "2") (pinfunction "2_2") (pintype "passive"))
      (node (ref "U1") (pin "24") (pinfunction "(PCINT21/TDI)PC5_24") (pintype "output"))
    )
    (net (code "28") (name "DIS_A1") (class "Default")
      (node (ref "DS1") (pin "14") (pinfunction "A_14") (pintype "bidirectional"))
      (node (ref "R12") (pin "1") (pinfunction "1_1") (pintype "passive"))
    )
    (net (code "29") (name "DIS_A2") (class "Default")
      (node (ref "DS2") (pin "14") (pinfunction "A_14") (pintype "bidirectional"))
      (node (ref "R46") (pin "1") (pinfunction "1_1") (pintype "passive"))
    )
    (net (code "30") (name "DIS_B1") (class "Default")
      (node (ref "DS1") (pin "16") (pinfunction "B_16") (pintype "bidirectional"))
      (node (ref "R13") (pin "1") (pinfunction "1_1") (pintype "passive"))
    )
    (net (code "31") (name "DIS_B2") (class "Default")
      (node (ref "DS2") (pin "16") (pinfunction "B_16") (pintype "bidirectional"))
      (node (ref "R47") (pin "1") (pinfunction "1_1") (pintype "passive"))
    )
    (net (code "32") (name "DIS_C1") (class "Default")
      (node (ref "DS1") (pin "13") (pinfunction "C_13") (pintype "bidirectional"))
      (node (ref "R14") (pin "1") (pinfunction "1_1") (pintype "passive"))
    )
    (net (code "33") (name "DIS_C2") (class "Default")
      (node (ref "DS2") (pin "13") (pinfunction "C_13") (pintype "bidirectional"))
      (node (ref "R48") (pin "1") (pinfunction "1_1") (pintype "passive"))
    )
    (net (code "34") (name "DIS_COL1") (class "Default")
      (node (ref "DS1") (pin "12") (pinfunction "COL-C_12") (pintype "bidirectional"))
      (node (ref "R20") (pin "1") (pinfunction "1_1") (pintype "passive"))
    )
    (net (code "35") (name "DIS_COL2") (class "Default")
      (node (ref "DS2") (pin "12") (pinfunction "COL-C_12") (pintype "bidirectional"))
      (node (ref "R54") (pin "1") (pinfunction "1_1") (pintype "passive"))
    )
    (net (code "36") (name "DIS_D1") (class "Default")
      (node (ref "DS1") (pin "3") (pinfunction "D_3") (pintype "bidirectional"))
      (node (ref "R15") (pin "1") (pinfunction "1_1") (pintype "passive"))
    )
    (net (code "37") (name "DIS_D2") (class "Default")
      (node (ref "DS2") (pin "3") (pinfunction "D_3") (pintype "bidirectional"))
      (node (ref "R49") (pin "1") (pinfunction "1_1") (pintype "passive"))
    )
    (net (code "38") (name "DIS_DIG1_1") (class "Default")
      (node (ref "DS1") (pin "1") (pinfunction "DIG1_1") (pintype "bidirectional"))
      (node (ref "Q1") (pin "3") (pinfunction "D_3") (pintype "bidirectional"))
    )
    (net (code "39") (name "DIS_DIG1_2") (class "Default")
      (node (ref "DS2") (pin "1") (pinfunction "DIG1_1") (pintype "bidirectional"))
      (node (ref "Q13") (pin "3") (pinfunction "D_3") (pintype "bidirectional"))
    )
    (net (code "40") (name "DIS_DIG2_1") (class "Default")
      (node (ref "DS1") (pin "2") (pinfunction "DIG2_2") (pintype "bidirectional"))
      (node (ref "Q2") (pin "3") (pinfunction "D_3") (pintype "bidirectional"))
    )
    (net (code "41") (name "DIS_DIG2_2") (class "Default")
      (node (ref "DS2") (pin "2") (pinfunction "DIG2_2") (pintype "bidirectional"))
      (node (ref "Q14") (pin "3") (pinfunction "D_3") (pintype "bidirectional"))
    )
    (net (code "42") (name "DIS_DIG3_1") (class "Default")
      (node (ref "DS1") (pin "6") (pinfunction "DIG3_6") (pintype "bidirectional"))
      (node (ref "Q3") (pin "3") (pinfunction "D_3") (pintype "bidirectional"))
    )
    (net (code "43") (name "DIS_DIG3_2") (class "Default")
      (node (ref "DS2") (pin "6") (pinfunction "DIG3_6") (pintype "bidirectional"))
      (node (ref "Q15") (pin "3") (pinfunction "D_3") (pintype "bidirectional"))
    )
    (net (code "44") (name "DIS_DIG4_1") (class "Default")
      (node (ref "DS1") (pin "8") (pinfunction "DIG4_8") (pintype "bidirectional"))
      (node (ref "Q4") (pin "3") (pinfunction "D_3") (pintype "bidirectional"))
    )
    (net (code "45") (name "DIS_DIG4_2") (class "Default")
      (node (ref "DS2") (pin "8") (pinfunction "DIG4_8") (pintype "bidirectional"))
      (node (ref "Q16") (pin "3") (pinfunction "D_3") (pintype "bidirectional"))
    )
    (net (code "46") (name "DIS_DP1") (class "Default")
      (node (ref "DS1") (pin "7") (pinfunction "DP_7") (pintype "bidirectional"))
      (node (ref "R19") (pin "1") (pinfunction "1_1") (pintype "passive"))
    )
    (net (code "47") (name "DIS_DP2") (class "Default")
      (node (ref "DS2") (pin "7") (pinfunction "DP_7") (pintype "bidirectional"))
      (node (ref "R53") (pin "1") (pinfunction "1_1") (pintype "passive"))
    )
    (net (code "48") (name "DIS_E1") (class "Default")
      (node (ref "DS1") (pin "5") (pinfunction "E_5") (pintype "bidirectional"))
      (node (ref "R16") (pin "1") (pinfunction "1_1") (pintype "passive"))
    )
    (net (code "49") (name "DIS_E2") (class "Default")
      (node (ref "DS2") (pin "5") (pinfunction "E_5") (pintype "bidirectional"))
      (node (ref "R50") (pin "1") (pinfunction "1_1") (pintype "passive"))
    )
    (net (code "50") (name "DIS_F1") (class "Default")
      (node (ref "DS1") (pin "11") (pinfunction "F_11") (pintype "bidirectional"))
      (node (ref "R17") (pin "1") (pinfunction "1_1") (pintype "passive"))
    )
    (net (code "51") (name "DIS_F2") (class "Default")
      (node (ref "DS2") (pin "11") (pinfunction "F_11") (pintype "bidirectional"))
      (node (ref "R51") (pin "1") (pinfunction "1_1") (pintype "passive"))
    )
    (net (code "52") (name "DIS_G1") (class "Default")
      (node (ref "DS1") (pin "15") (pinfunction "G_15") (pintype "bidirectional"))
      (node (ref "R18") (pin "1") (pinfunction "1_1") (pintype "passive"))
    )
    (net (code "53") (name "DIS_G2") (class "Default")
      (node (ref "DS2") (pin "15") (pinfunction "G_15") (pintype "bidirectional"))
      (node (ref "R52") (pin "1") (pinfunction "1_1") (pintype "passive"))
    )
    (net (code "54") (name "DIS_POS1") (class "Default")
      (node (ref "DS1") (pin "9") (pinfunction "APOS-C_9") (pintype "bidirectional"))
      (node (ref "R21") (pin "1") (pinfunction "1_1") (pintype "passive"))
    )
    (net (code "55") (name "DIS_POS2") (class "Default")
      (node (ref "DS2") (pin "9") (pinfunction "APOS-C_9") (pintype "bidirectional"))
      (node (ref "R55") (pin "1") (pinfunction "1_1") (pintype "passive"))
    )
    (net (code "56") (name "GND") (class "Default")
      (node (ref "C1") (pin "1") (pinfunction "1_1") (pintype "passive"))
      (node (ref "C10") (pin "2") (pinfunction "2_2") (pintype "passive"))
      (node (ref "C11") (pin "2") (pinfunction "2_2") (pintype "passive"))
      (node (ref "C12") (pin "2") (pinfunction "2_2") (pintype "passive"))
      (node (ref "C13") (pin "2") (pinfunction "2_2") (pintype "passive"))
      (node (ref "C2") (pin "1") (pinfunction "1_1") (pintype "passive"))
      (node (ref "C3") (pin "2") (pinfunction "2_2") (pintype "passive"))
      (node (ref "C4") (pin "2") (pinfunction "2_2") (pintype "passive"))
      (node (ref "C5") (pin "2") (pinfunction "2_2") (pintype "passive"))
      (node (ref "C6") (pin "2") (pinfunction "2_2") (pintype "passive"))
      (node (ref "C8") (pin "2") (pinfunction "2_2") (pintype "passive"))
      (node (ref "C9") (pin "2") (pinfunction "2_2") (pintype "passive"))
      (node (ref "D1") (pin "CATHODE") (pinfunction "CATHODE_CATHODE") (pintype "power_in"))
      (node (ref "D10") (pin "CATHODE") (pinfunction "CATHODE_CATHODE") (pintype "power_in"))
      (node (ref "D11") (pin "CATHODE") (pinfunction "CATHODE_CATHODE") (pintype "power_in"))
      (node (ref "D12") (pin "CATHODE") (pinfunction "CATHODE_CATHODE") (pintype "power_in"))
      (node (ref "D13") (pin "CATHODE") (pinfunction "CATHODE_CATHODE") (pintype "power_in"))
      (node (ref "D2") (pin "CATHODE") (pinfunction "CATHODE_CATHODE") (pintype "power_in"))
      (node (ref "D3") (pin "CATHODE") (pinfunction "CATHODE_CATHODE") (pintype "power_in"))
      (node (ref "D4") (pin "CATHODE") (pinfunction "CATHODE_CATHODE") (pintype "power_in"))
      (node (ref "D5") (pin "CATHODE") (pinfunction "CATHODE_CATHODE") (pintype "power_in"))
      (node (ref "D6") (pin "CATHODE") (pinfunction "CATHODE_CATHODE") (pintype "power_in"))
      (node (ref "D7") (pin "CATHODE") (pinfunction "CATHODE_CATHODE") (pintype "power_in"))
      (node (ref "D8") (pin "CATHODE") (pinfunction "CATHODE_CATHODE") (pintype "power_in"))
      (node (ref "DS1") (pin "10") (pinfunction "APOS-A_10") (pintype "bidirectional"))
      (node (ref "DS1") (pin "4") (pinfunction "COL-A_4") (pintype "bidirectional"))
      (node (ref "DS2") (pin "10") (pinfunction "APOS-A_10") (pintype "bidirectional"))
      (node (ref "DS2") (pin "4") (pinfunction "COL-A_4") (pintype "bidirectional"))
      (node (ref "ISP1") (pin "6") (pinfunction "GND_6") (pintype "power_in"))
      (node (ref "ISP2") (pin "6") (pinfunction "GND_6") (pintype "power_in"))
      (node (ref "ISP3") (pin "6") (pinfunction "GND_6") (pintype "power_in"))
      (node (ref "J1") (pin "2") (pinfunction "2_2") (pintype "bidirectional"))
      (node (ref "Q1") (pin "2") (pinfunction "S_2") (pintype "bidirectional"))
      (node (ref "Q13") (pin "2") (pinfunction "S_2") (pintype "bidirectional"))
      (node (ref "Q14") (pin "2") (pinfunction "S_2") (pintype "bidirectional"))
      (node (ref "Q15") (pin "2") (pinfunction "S_2") (pintype "bidirectional"))
      (node (ref "Q16") (pin "2") (pinfunction "S_2") (pintype "bidirectional"))
      (node (ref "Q2") (pin "2") (pinfunction "S_2") (pintype "bidirectional"))
      (node (ref "Q3") (pin "2") (pinfunction "S_2") (pintype "bidirectional"))
      (node (ref "Q4") (pin "2") (pinfunction "S_2") (pintype "bidirectional"))
      (node (ref "Q5") (pin "2") (pinfunction "S_2") (pintype "bidirectional"))
      (node (ref "R22") (pin "1") (pinfunction "1_1") (pintype "passive"))
      (node (ref "R24") (pin "1") (pinfunction "1_1") (pintype "passive"))
      (node (ref "S1") (pin "1") (pinfunction "1_1") (pintype "passive"))
      (node (ref "S1") (pin "2") (pinfunction "2_2") (pintype "passive"))
      (node (ref "S1") (pin "3") (pinfunction "3_3") (pintype "passive"))
      (node (ref "S1") (pin "4") (pinfunction "4_4") (pintype "passive"))
      (node (ref "S1") (pin "5") (pinfunction "5_5") (pintype "passive"))
      (node (ref "S1") (pin "6") (pinfunction "6_6") (pintype "passive"))
      (node (ref "S1") (pin "7") (pinfunction "7_7") (pintype "passive"))
      (node (ref "S1") (pin "8") (pinfunction "8_8") (pintype "passive"))
      (node (ref "S2") (pin "3") (pinfunction "3_3") (pintype "bidirectional"))
      (node (ref "S2") (pin "4") (pinfunction "4_4") (pintype "bidirectional"))
      (node (ref "S3") (pin "3") (pinfunction "3_3") (pintype "bidirectional"))
      (node (ref "S3") (pin "4") (pinfunction "4_4") (pintype "bidirectional"))
      (node (ref "S4") (pin "3") (pinfunction "3_3") (pintype "bidirectional"))
      (node (ref "S4") (pin "4") (pinfunction "4_4") (pintype "bidirectional"))
      (node (ref "S5") (pin "3") (pinfunction "S_3") (pintype "passive"))
      (node (ref "U1") (pin "18") (pinfunction "GND_18") (pintype "power_in"))
      (node (ref "U1") (pin "28") (pinfunction "GND_28") (pintype "power_in"))
      (node (ref "U1") (pin "39") (pinfunction "GND_39") (pintype "power_in"))
      (node (ref "U1") (pin "6") (pinfunction "GND_6") (pintype "power_in"))
      (node (ref "U1") (pin "TH") (pinfunction "EXP_TH") (pintype "power_in"))
      (node (ref "U2") (pin "10") (pinfunction "SER_10") (pintype "input"))
      (node (ref "U2") (pin "8") (pinfunction "GND_8") (pintype "power_in"))
      (node (ref "U4") (pin "21") (pinfunction "GND_21") (pintype "power_in"))
      (node (ref "U4") (pin "3") (pinfunction "GND_3") (pintype "power_in"))
      (node (ref "U4") (pin "5") (pinfunction "GND_5") (pintype "power_in"))
      (node (ref "U4") (pin "TH") (pinfunction "GND_TH") (pintype "power_in"))
      (node (ref "U5") (pin "1") (pinfunction "AGND_1") (pintype "power_in"))
      (node (ref "U5") (pin "EP@1") (pinfunction "PGND_EP@1") (pintype "power_in"))
      (node (ref "U5") (pin "EP@2") (pinfunction "PGND_EP@2") (pintype "power_in"))
      (node (ref "U5") (pin "EP@3") (pinfunction "PGND_EP@3") (pintype "power_in"))
      (node (ref "U7") (pin "21") (pinfunction "GND_21") (pintype "power_in"))
      (node (ref "U7") (pin "3") (pinfunction "GND_3") (pintype "power_in"))
      (node (ref "U7") (pin "5") (pinfunction "GND_5") (pintype "power_in"))
      (node (ref "U7") (pin "TH") (pinfunction "GND_TH") (pintype "power_in"))
    )
    (net (code "57") (name "HOLD") (class "Default")
      (node (ref "R25") (pin "1") (pinfunction "1_1") (pintype "passive"))
      (node (ref "S4") (pin "1") (pinfunction "1_1") (pintype "bidirectional"))
      (node (ref "S4") (pin "2") (pinfunction "2_2") (pintype "bidirectional"))
      (node (ref "U1") (pin "30") (pinfunction "(PCINT7/ADC7)PA7_30") (pintype "bidirectional"))
    )
    (net (code "58") (name "MCU_A1") (class "Default")
      (node (ref "R12") (pin "2") (pinfunction "2_2") (pintype "passive"))
      (node (ref "U4") (pin "32") (pinfunction "(PCINT18/INT0)PD2_32") (pintype "bidirectional"))
    )
    (net (code "59") (name "MCU_A2") (class "Default")
      (node (ref "R46") (pin "2") (pinfunction "2_2") (pintype "passive"))
      (node (ref "U7") (pin "32") (pinfunction "(PCINT18/INT0)PD2_32") (pintype "bidirectional"))
    )
    (net (code "60") (name "MCU_B1") (class "Default")
      (node (ref "R13") (pin "2") (pinfunction "2_2") (pintype "passive"))
      (node (ref "U4") (pin "1") (pinfunction "(PCINT19/INT1)PD3_1") (pintype "bidirectional"))
    )
    (net (code "61") (name "MCU_B2") (class "Default")
      (node (ref "R47") (pin "2") (pinfunction "2_2") (pintype "passive"))
      (node (ref "U7") (pin "1") (pinfunction "(PCINT19/INT1)PD3_1") (pintype "bidirectional"))
    )
    (net (code "62") (name "MCU_C1") (class "Default")
      (node (ref "R14") (pin "2") (pinfunction "2_2") (pintype "passive"))
      (node (ref "U4") (pin "2") (pinfunction "(PCINT20/XCK/T0)PD4_2") (pintype "bidirectional"))
    )
    (net (code "63") (name "MCU_C2") (class "Default")
      (node (ref "R48") (pin "2") (pinfunction "2_2") (pintype "passive"))
      (node (ref "U7") (pin "2") (pinfunction "(PCINT20/XCK/T0)PD4_2") (pintype "bidirectional"))
    )
    (net (code "64") (name "MCU_COL1") (class "Default")
      (node (ref "R20") (pin "2") (pinfunction "2_2") (pintype "passive"))
      (node (ref "U4") (pin "12") (pinfunction "(PCINT0/CLKO/ICP1)PB0_12") (pintype "bidirectional"))
    )
    (net (code "65") (name "MCU_COL2") (class "Default")
      (node (ref "R54") (pin "2") (pinfunction "2_2") (pintype "passive"))
      (node (ref "U7") (pin "12") (pinfunction "(PCINT0/CLKO/ICP1)PB0_12") (pintype "bidirectional"))
    )
    (net (code "66") (name "MCU_D1") (class "Default")
      (node (ref "R15") (pin "2") (pinfunction "2_2") (pintype "passive"))
      (node (ref "U4") (pin "9") (pinfunction "(PCINT21/OC0B/T1)PD5_9") (pintype "bidirectional"))
    )
    (net (code "67") (name "MCU_D2") (class "Default")
      (node (ref "R49") (pin "2") (pinfunction "2_2") (pintype "passive"))
      (node (ref "U7") (pin "9") (pinfunction "(PCINT21/OC0B/T1)PD5_9") (pintype "bidirectional"))
    )
    (net (code "68") (name "MCU_DIG1_1") (class "Default")
      (node (ref "Q1") (pin "1") (pinfunction "G_1") (pintype "bidirectional"))
      (node (ref "U4") (pin "26") (pinfunction "(PCINT11/ADC3)PC3_26") (pintype "bidirectional"))
    )
    (net (code "69") (name "MCU_DIG1_2") (class "Default")
      (node (ref "Q13") (pin "1") (pinfunction "G_1") (pintype "bidirectional"))
      (node (ref "U7") (pin "26") (pinfunction "(PCINT11/ADC3)PC3_26") (pintype "bidirectional"))
    )
    (net (code "70") (name "MCU_DIG2_1") (class "Default")
      (node (ref "Q2") (pin "1") (pinfunction "G_1") (pintype "bidirectional"))
      (node (ref "U4") (pin "25") (pinfunction "(PCINT10/ADC2)PC2_25") (pintype "bidirectional"))
    )
    (net (code "71") (name "MCU_DIG2_2") (class "Default")
      (node (ref "Q14") (pin "1") (pinfunction "G_1") (pintype "bidirectional"))
      (node (ref "U7") (pin "25") (pinfunction "(PCINT10/ADC2)PC2_25") (pintype "bidirectional"))
    )
    (net (code "72") (name "MCU_DIG3_1") (class "Default")
      (node (ref "Q3") (pin "1") (pinfunction "G_1") (pintype "bidirectional"))
      (node (ref "U4") (pin "24") (pinfunction "(PCINT9/ADC1)PC1_24") (pintype "bidirectional"))
    )
    (net (code "73") (name "MCU_DIG3_2") (class "Default")
      (node (ref "Q15") (pin "1") (pinfunction "G_1") (pintype "bidirectional"))
      (node (ref "U7") (pin "24") (pinfunction "(PCINT9/ADC1)PC1_24") (pintype "bidirectional"))
    )
    (net (code "74") (name "MCU_DIG4_1") (class "Default")
      (node (ref "Q4") (pin "1") (pinfunction "G_1") (pintype "bidirectional"))
      (node (ref "U4") (pin "23") (pinfunction "(PCINT8/ADC0)PC0_23") (pintype "bidirectional"))
    )
    (net (code "75") (name "MCU_DIG4_2") (class "Default")
      (node (ref "Q16") (pin "1") (pinfunction "G_1") (pintype "bidirectional"))
      (node (ref "U7") (pin "23") (pinfunction "(PCINT8/ADC0)PC0_23") (pintype "bidirectional"))
    )
    (net (code "76") (name "MCU_DP1") (class "Default")
      (node (ref "R19") (pin "2") (pinfunction "2_2") (pintype "passive"))
      (node (ref "U4") (pin "14") (pinfunction "(PCINT2/~{SS}/OC1B)PB2_14") (pintype "bidirectional"))
    )
    (net (code "77") (name "MCU_DP2") (class "Default")
      (node (ref "R53") (pin "2") (pinfunction "2_2") (pintype "passive"))
      (node (ref "U7") (pin "14") (pinfunction "(PCINT2/~{SS}/OC1B)PB2_14") (pintype "bidirectional"))
    )
    (net (code "78") (name "MCU_E1") (class "Default")
      (node (ref "R16") (pin "2") (pinfunction "2_2") (pintype "passive"))
      (node (ref "U4") (pin "10") (pinfunction "(PCINT22/OC0A/AIN0)PD6_10") (pintype "bidirectional"))
    )
    (net (code "79") (name "MCU_E2") (class "Default")
      (node (ref "R50") (pin "2") (pinfunction "2_2") (pintype "passive"))
      (node (ref "U7") (pin "10") (pinfunction "(PCINT22/OC0A/AIN0)PD6_10") (pintype "bidirectional"))
    )
    (net (code "80") (name "MCU_F1") (class "Default")
      (node (ref "R17") (pin "2") (pinfunction "2_2") (pintype "passive"))
      (node (ref "U4") (pin "11") (pinfunction "(PCINT23/AIN1)PD7_11") (pintype "bidirectional"))
    )
    (net (code "81") (name "MCU_F2") (class "Default")
      (node (ref "R51") (pin "2") (pinfunction "2_2") (pintype "passive"))
      (node (ref "U7") (pin "11") (pinfunction "(PCINT23/AIN1)PD7_11") (pintype "bidirectional"))
    )
    (net (code "82") (name "MCU_G1") (class "Default")
      (node (ref "R18") (pin "2") (pinfunction "2_2") (pintype "passive"))
      (node (ref "U4") (pin "7") (pinfunction "(PCINT6/XTAL1/TOSC1)PB6_7") (pintype "bidirectional"))
    )
    (net (code "83") (name "MCU_G2") (class "Default")
      (node (ref "R52") (pin "2") (pinfunction "2_2") (pintype "passive"))
      (node (ref "U7") (pin "7") (pinfunction "(PCINT6/XTAL1/TOSC1)PB6_7") (pintype "bidirectional"))
    )
    (net (code "84") (name "MCU_POS1") (class "Default")
      (node (ref "R21") (pin "2") (pinfunction "2_2") (pintype "passive"))
      (node (ref "U4") (pin "13") (pinfunction "(PCINT1/OC1A)PB1_13") (pintype "bidirectional"))
    )
    (net (code "85") (name "MCU_POS2") (class "Default")
      (node (ref "R55") (pin "2") (pinfunction "2_2") (pintype "passive"))
      (node (ref "U7") (pin "13") (pinfunction "(PCINT1/OC1A)PB1_13") (pintype "bidirectional"))
    )
    (net (code "86") (name "MISO") (class "Default")
      (node (ref "ISP1") (pin "1") (pinfunction "MISO_1") (pintype "input"))
      (node (ref "U1") (pin "2") (pinfunction "(PCINT14/MISO)PB6_2") (pintype "bidirectional"))
    )
    (net (code "87") (name "MISO_A") (class "Default")
      (node (ref "ISP2") (pin "1") (pinfunction "MISO_1") (pintype "input"))
      (node (ref "U4") (pin "16") (pinfunction "(PCINT4/MISO)PB4_16") (pintype "bidirectional"))
    )
    (net (code "88") (name "MISO_B") (class "Default")
      (node (ref "ISP3") (pin "1") (pinfunction "MISO_1") (pintype "input"))
      (node (ref "U7") (pin "16") (pinfunction "(PCINT4/MISO)PB4_16") (pintype "bidirectional"))
    )
    (net (code "89") (name "MOSI") (class "Default")
      (node (ref "ISP1") (pin "4") (pinfunction "MOSI_4") (pintype "output"))
      (node (ref "U1") (pin "1") (pinfunction "(PCINT13/MOSI)PB5_1") (pintype "bidirectional"))
    )
    (net (code "90") (name "MOSI_A") (class "Default")
      (node (ref "ISP2") (pin "4") (pinfunction "MOSI_4") (pintype "output"))
      (node (ref "U4") (pin "15") (pinfunction "(PCINT3/OC2A/MOSI)PB3_15") (pintype "bidirectional"))
    )
    (net (code "91") (name "MOSI_B") (class "Default")
      (node (ref "ISP3") (pin "4") (pinfunction "MOSI_4") (pintype "output"))
      (node (ref "U7") (pin "15") (pinfunction "(PCINT3/OC2A/MOSI)PB3_15") (pintype "bidirectional"))
    )
    (net (code "92") (name "Net-(D1-PadANODE)") (class "Default")
      (node (ref "D1") (pin "ANODE") (pinfunction "ANODE_ANODE") (pintype "power_in"))
      (node (ref "R26") (pin "1") (pinfunction "1_1") (pintype "passive"))
    )
    (net (code "93") (name "Net-(D2-PadANODE)") (class "Default")
      (node (ref "D2") (pin "ANODE") (pinfunction "ANODE_ANODE") (pintype "power_in"))
      (node (ref "R27") (pin "1") (pinfunction "1_1") (pintype "passive"))
    )
    (net (code "94") (name "Net-(D3-PadANODE)") (class "Default")
      (node (ref "D3") (pin "ANODE") (pinfunction "ANODE_ANODE") (pintype "power_in"))
      (node (ref "R28") (pin "1") (pinfunction "1_1") (pintype "passive"))
    )
    (net (code "95") (name "Net-(D4-PadANODE)") (class "Default")
      (node (ref "D4") (pin "ANODE") (pinfunction "ANODE_ANODE") (pintype "power_in"))
      (node (ref "R29") (pin "1") (pinfunction "1_1") (pintype "passive"))
    )
    (net (code "96") (name "Net-(D5-PadANODE)") (class "Default")
      (node (ref "D5") (pin "ANODE") (pinfunction "ANODE_ANODE") (pintype "power_in"))
      (node (ref "R30") (pin "1") (pinfunction "1_1") (pintype "passive"))
    )
    (net (code "97") (name "Net-(D6-PadANODE)") (class "Default")
      (node (ref "D6") (pin "ANODE") (pinfunction "ANODE_ANODE") (pintype "power_in"))
      (node (ref "R31") (pin "1") (pinfunction "1_1") (pintype "passive"))
    )
    (net (code "98") (name "Net-(D7-PadANODE)") (class "Default")
      (node (ref "D7") (pin "ANODE") (pinfunction "ANODE_ANODE") (pintype "power_in"))
      (node (ref "R32") (pin "1") (pinfunction "1_1") (pintype "passive"))
    )
    (net (code "99") (name "Net-(D8-PadANODE)") (class "Default")
      (node (ref "D8") (pin "ANODE") (pinfunction "ANODE_ANODE") (pintype "power_in"))
      (node (ref "R33") (pin "1") (pinfunction "1_1") (pintype "passive"))
    )
    (net (code "100") (name "Net-(D9-PadCATHODE)") (class "Default")
      (node (ref "D9") (pin "CATHODE") (pinfunction "CATHODE_CATHODE") (pintype "power_in"))
      (node (ref "R34") (pin "1") (pinfunction "1_1") (pintype "passive"))
    )
    (net (code "101") (name "Net-(D10-PadANODE)") (class "Default")
      (node (ref "D10") (pin "ANODE") (pinfunction "ANODE_ANODE") (pintype "power_in"))
      (node (ref "R35") (pin "1") (pinfunction "1_1") (pintype "passive"))
    )
    (net (code "102") (name "Net-(D11-PadANODE)") (class "Default")
      (node (ref "D11") (pin "ANODE") (pinfunction "ANODE_ANODE") (pintype "power_in"))
      (node (ref "R36") (pin "1") (pinfunction "1_1") (pintype "passive"))
    )
    (net (code "103") (name "Net-(D12-PadANODE)") (class "Default")
      (node (ref "D12") (pin "ANODE") (pinfunction "ANODE_ANODE") (pintype "power_in"))
      (node (ref "R38") (pin "1") (pinfunction "1_1") (pintype "passive"))
    )
    (net (code "104") (name "Net-(D13-PadANODE)") (class "Default")
      (node (ref "D13") (pin "ANODE") (pinfunction "ANODE_ANODE") (pintype "power_in"))
      (node (ref "R39") (pin "1") (pinfunction "1_1") (pintype "passive"))
    )
    (net (code "105") (name "Net-(L1-2)") (class "Default")
      (node (ref "L1") (pin "P$2") (pinfunction "2_P$2") (pintype "passive"))
      (node (ref "U5") (pin "6") (pinfunction "SW_6") (pintype "power_in"))
      (node (ref "U5") (pin "7") (pinfunction "SW_7") (pintype "power_in"))
    )
    (net (code "106") (name "Net-(Q5-D)") (class "Default")
      (node (ref "BT1") (pin "NEG@1") (pinfunction "-_NEG@1") (pintype "power_in"))
      (node (ref "BT1") (pin "NEG@2") (pinfunction "-_NEG@2") (pintype "power_in"))
      (node (ref "D9") (pin "ANODE") (pinfunction "ANODE_ANODE") (pintype "power_in"))
      (node (ref "Q5") (pin "3") (pinfunction "D_3") (pintype "bidirectional"))
    )
    (net (code "107") (name "Net-(U1-(PCINT0{slash}ADC0)PA0)") (class "Default")
      (node (ref "R40") (pin "1") (pinfunction "1_1") (pintype "passive"))
      (node (ref "U1") (pin "37") (pinfunction "(PCINT0/ADC0)PA0_37") (pintype "bidirectional"))
    )
    (net (code "108") (name "Net-(U1-XTAL1)") (class "Default")
      (node (ref "C2") (pin "2") (pinfunction "2_2") (pintype "passive"))
      (node (ref "U1") (pin "8") (pinfunction "XTAL1_8") (pintype "bidirectional"))
      (node (ref "XTAL1") (pin "OSC1") (pinfunction "1_OSC1") (pintype "passive"))
    )
    (net (code "109") (name "Net-(U1-XTAL2)") (class "Default")
      (node (ref "C1") (pin "2") (pinfunction "2_2") (pintype "passive"))
      (node (ref "U1") (pin "7") (pinfunction "XTAL2_7") (pintype "bidirectional"))
      (node (ref "XTAL1") (pin "OSC2") (pinfunction "2_OSC2") (pintype "passive"))
    )
    (net (code "110") (name "Net-(U5-FB)") (class "Default")
      (node (ref "C7") (pin "2") (pinfunction "2_2") (pintype "passive"))
      (node (ref "R23") (pin "1") (pinfunction "1_1") (pintype "passive"))
      (node (ref "R24") (pin "2") (pinfunction "2_2") (pintype "passive"))
      (node (ref "U5") (pin "2") (pinfunction "FB_2") (pintype "input"))
    )
    (net (code "111") (name "PG") (class "Default")
      (node (ref "R36") (pin "2") (pinfunction "2_2") (pintype "passive"))
      (node (ref "U1") (pin "36") (pinfunction "(PCINT1/ADC1)PA1_36") (pintype "bidirectional"))
    )
    (net (code "112") (name "RX1") (class "Default")
      (node (ref "U1") (pin "10") (pinfunction "(PCINT25/TXD0)PD1_10") (pintype "bidirectional"))
      (node (ref "U4") (pin "30") (pinfunction "(PCINT16/RXD)PD0_30") (pintype "bidirectional"))
    )
    (net (code "113") (name "RX2") (class "Default")
      (node (ref "U1") (pin "12") (pinfunction "(PCINT27/INT1)PD3_12") (pintype "bidirectional"))
      (node (ref "U7") (pin "30") (pinfunction "(PCINT16/RXD)PD0_30") (pintype "bidirectional"))
    )
    (net (code "114") (name "SCK") (class "Default")
      (node (ref "ISP1") (pin "3") (pinfunction "SCK_3") (pintype "output"))
      (node (ref "U1") (pin "3") (pinfunction "(PCINT15/SCK)PB7_3") (pintype "bidirectional"))
    )
    (net (code "115") (name "SCK_A") (class "Default")
      (node (ref "ISP2") (pin "3") (pinfunction "SCK_3") (pintype "output"))
      (node (ref "U4") (pin "17") (pinfunction "(PCINT5/SCK)PB5_17") (pintype "bidirectional"))
    )
    (net (code "116") (name "SCK_B") (class "Default")
      (node (ref "ISP3") (pin "3") (pinfunction "SCK_3") (pintype "output"))
      (node (ref "U7") (pin "17") (pinfunction "(PCINT5/SCK)PB5_17") (pintype "bidirectional"))
    )
    (net (code "117") (name "SCL") (class "Default")
      (node (ref "J1") (pin "3") (pinfunction "3_3") (pintype "bidirectional"))
      (node (ref "U1") (pin "19") (pinfunction "(PCINT16/SCL)PC0_19") (pintype "output"))
    )
    (net (code "118") (name "SDA") (class "Default")
      (node (ref "J1") (pin "4") (pinfunction "4_4") (pintype "bidirectional"))
      (node (ref "U1") (pin "20") (pinfunction "(PCINT17/SDA)PC1_20") (pintype "output"))
    )
    (net (code "119") (name "STAT1") (class "Default")
      (node (ref "R39") (pin "2") (pinfunction "2_2") (pintype "passive"))
      (node (ref "U1") (pin "35") (pinfunction "(PCINT2/ADC2)PA2_35") (pintype "bidirectional"))
    )
    (net (code "120") (name "STAT2") (class "Default")
      (node (ref "R38") (pin "2") (pinfunction "2_2") (pintype "passive"))
      (node (ref "U1") (pin "34") (pinfunction "(PCINT3/ADC3)PA3_34") (pintype "bidirectional"))
    )
    (net (code "121") (name "TX1") (class "Default")
      (node (ref "U1") (pin "9") (pinfunction "(PCINT24/RXD0)PD0_9") (pintype "bidirectional"))
      (node (ref "U4") (pin "31") (pinfunction "(PCINT17/TXD)PD1_31") (pintype "bidirectional"))
    )
    (net (code "122") (name "TX2") (class "Default")
      (node (ref "U1") (pin "11") (pinfunction "(PCINT26/INT0)PD2_11") (pintype "bidirectional"))
      (node (ref "U7") (pin "31") (pinfunction "(PCINT17/TXD)PD1_31") (pintype "bidirectional"))
    )
    (net (code "123") (name "unconnected-(U1-(PCINT8{slash}XCK0{slash}T0)PB0-Pad40)") (class "Default")
      (node (ref "U1") (pin "40") (pinfunction "(PCINT8/XCK0/T0)PB0_40") (pintype "bidirectional"))
    )
    (net (code "124") (name "unconnected-(U1-(PCINT9{slash}CLKO{slash}T1)PB1-Pad41)") (class "Default")
      (node (ref "U1") (pin "41") (pinfunction "(PCINT9/CLKO/T1)PB1_41") (pintype "bidirectional"))
    )
    (net (code "125") (name "unconnected-(U1-(PCINT10{slash}INT2{slash}AIN0)PB2-Pad42)") (class "Default")
      (node (ref "U1") (pin "42") (pinfunction "(PCINT10/INT2/AIN0)PB2_42") (pintype "bidirectional"))
    )
    (net (code "126") (name "unconnected-(U1-(PCINT11{slash}OC0A{slash}AIN1)PB3-Pad43)") (class "Default")
      (node (ref "U1") (pin "43") (pinfunction "(PCINT11/OC0A/AIN1)PB3_43") (pintype "bidirectional"))
    )
    (net (code "127") (name "unconnected-(U1-(PCINT12{slash}OC0B{slash}~{SS})PB4-Pad44)") (class "Default")
      (node (ref "U1") (pin "44") (pinfunction "(PCINT12/OC0B/~{SS})PB4_44") (pintype "bidirectional"))
    )
    (net (code "128") (name "unconnected-(U2-CLK_INH-Pad15)") (class "Default")
      (node (ref "U2") (pin "15") (pinfunction "CLK_INH_15") (pintype "input"))
    )
    (net (code "129") (name "unconnected-(U2-~{QH}-Pad7)") (class "Default")
      (node (ref "U2") (pin "7") (pinfunction "~{QH}_7") (pintype "input"))
    )
    (net (code "130") (name "unconnected-(U4-(PCINT7{slash}XTAL2{slash}TOSC2)PB7-Pad8)") (class "Default")
      (node (ref "U4") (pin "8") (pinfunction "(PCINT7/XTAL2/TOSC2)PB7_8") (pintype "bidirectional"))
    )
    (net (code "131") (name "unconnected-(U4-(PCINT12{slash}ADC4{slash}SDA)PC4-Pad27)") (class "Default")
      (node (ref "U4") (pin "27") (pinfunction "(PCINT12/ADC4/SDA)PC4_27") (pintype "bidirectional"))
    )
    (net (code "132") (name "unconnected-(U4-(PCINT13{slash}ADC5{slash}SCL)PC5-Pad28)") (class "Default")
      (node (ref "U4") (pin "28") (pinfunction "(PCINT13/ADC5/SCL)PC5_28") (pintype "bidirectional"))
    )
    (net (code "133") (name "unconnected-(U4-ADC6-Pad19)") (class "Default")
      (node (ref "U4") (pin "19") (pinfunction "ADC6_19") (pintype "input"))
    )
    (net (code "134") (name "unconnected-(U4-ADC7-Pad22)") (class "Default")
      (node (ref "U4") (pin "22") (pinfunction "ADC7_22") (pintype "input"))
    )
    (net (code "135") (name "unconnected-(U7-(PCINT7{slash}XTAL2{slash}TOSC2)PB7-Pad8)") (class "Default")
      (node (ref "U7") (pin "8") (pinfunction "(PCINT7/XTAL2/TOSC2)PB7_8") (pintype "bidirectional"))
    )
    (net (code "136") (name "unconnected-(U7-(PCINT12{slash}ADC4{slash}SDA)PC4-Pad27)") (class "Default")
      (node (ref "U7") (pin "27") (pinfunction "(PCINT12/ADC4/SDA)PC4_27") (pintype "bidirectional"))
    )
    (net (code "137") (name "unconnected-(U7-(PCINT13{slash}ADC5{slash}SCL)PC5-Pad28)") (class "Default")
      (node (ref "U7") (pin "28") (pinfunction "(PCINT13/ADC5/SCL)PC5_28") (pintype "bidirectional"))
    )
    (net (code "138") (name "unconnected-(U7-ADC6-Pad19)") (class "Default")
      (node (ref "U7") (pin "19") (pinfunction "ADC6_19") (pintype "input"))
    )
    (net (code "139") (name "unconnected-(U7-ADC7-Pad22)") (class "Default")
      (node (ref "U7") (pin "22") (pinfunction "ADC7_22") (pintype "input"))
    )
  )
)
